# smoothieboard.net
KiCad netlist of a schematic drawn in EAGLE
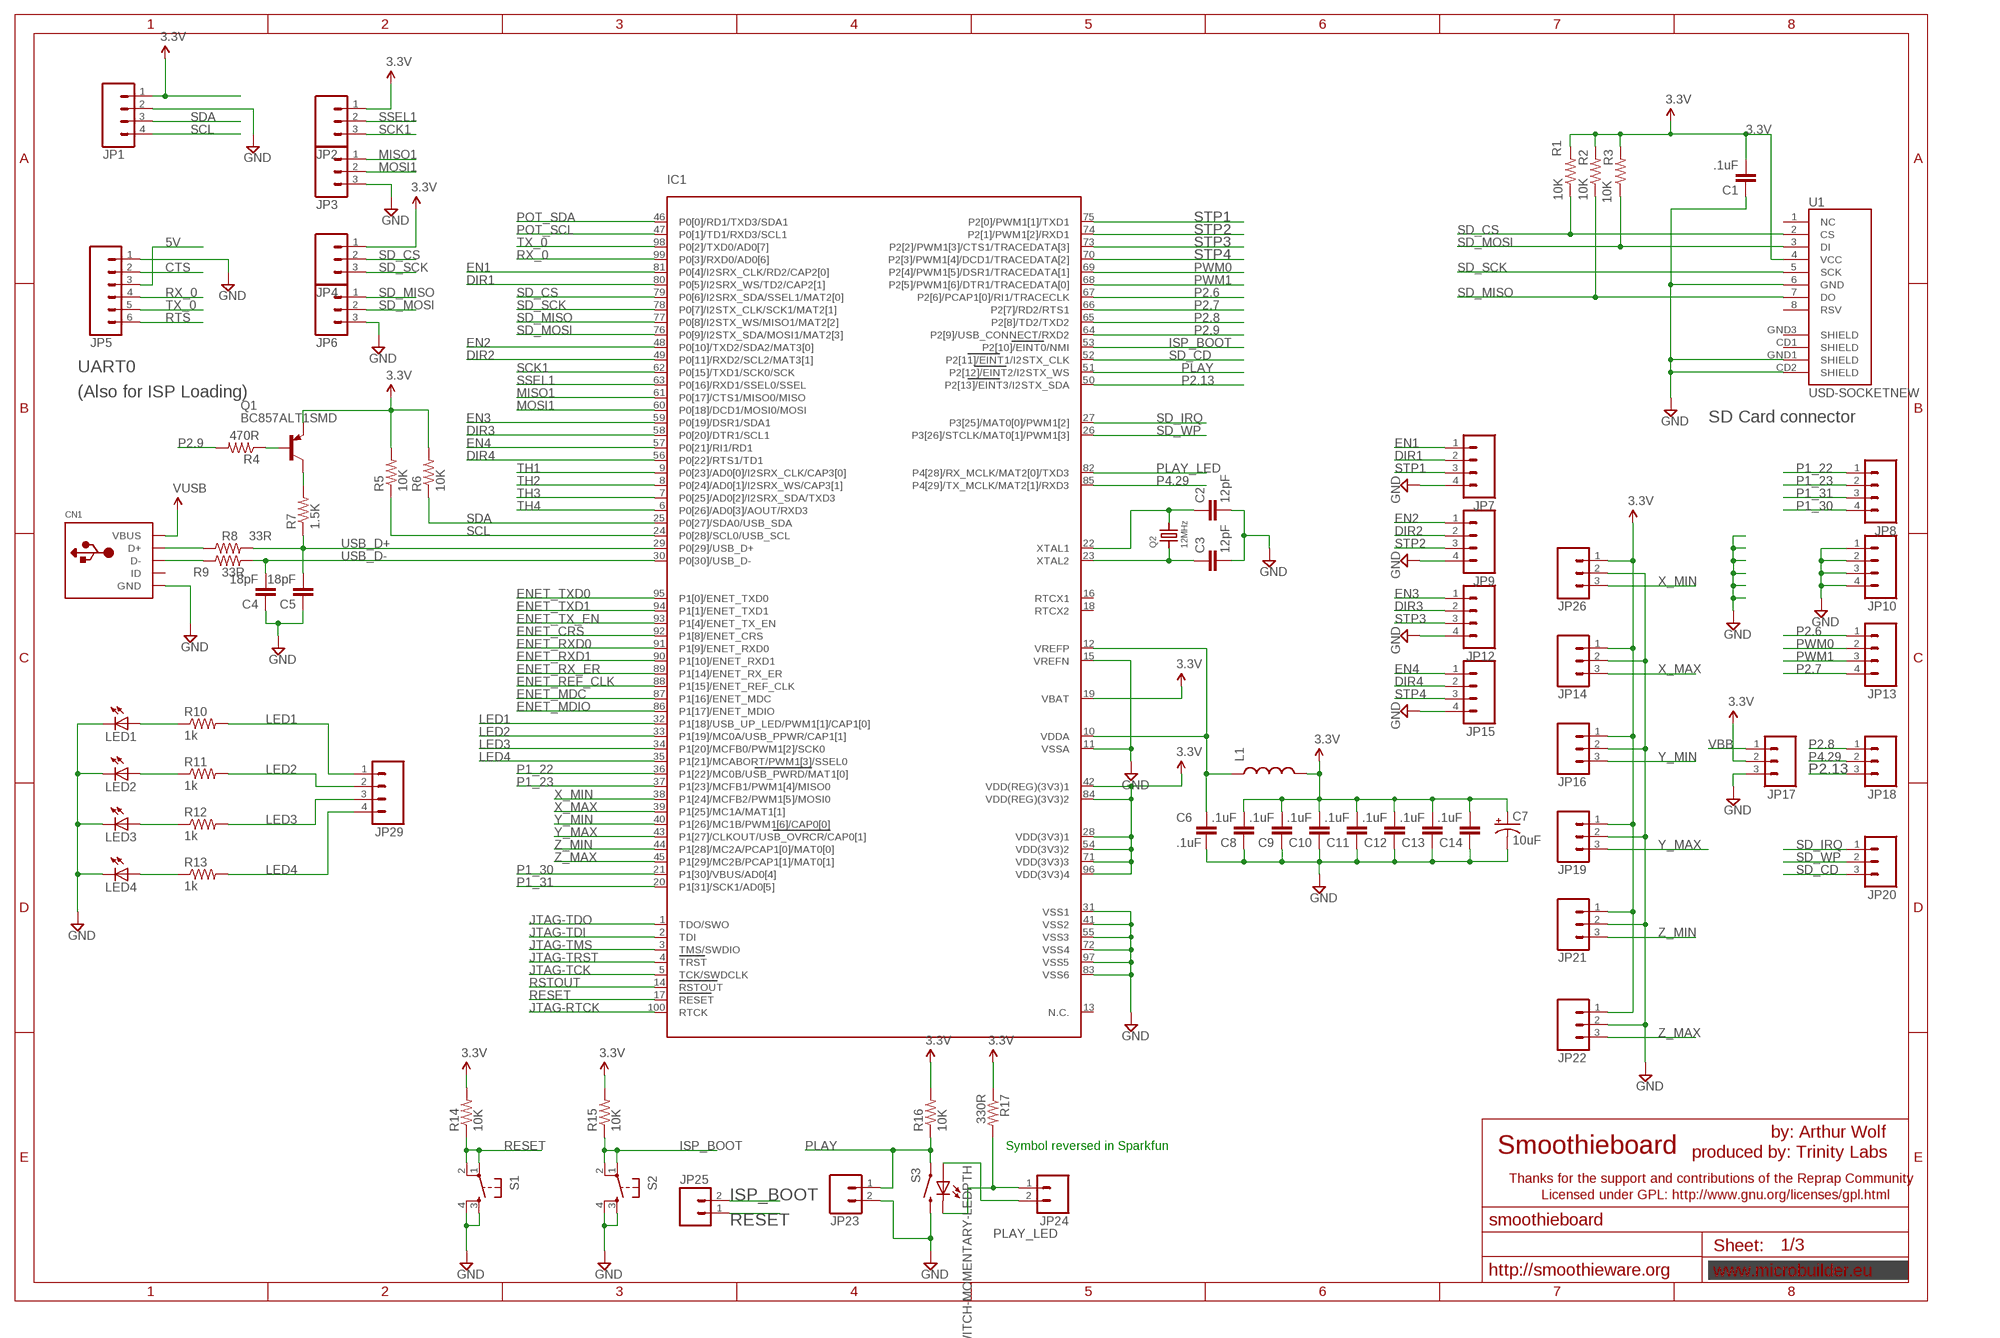
[diagram p0: schematic, sheet 1]
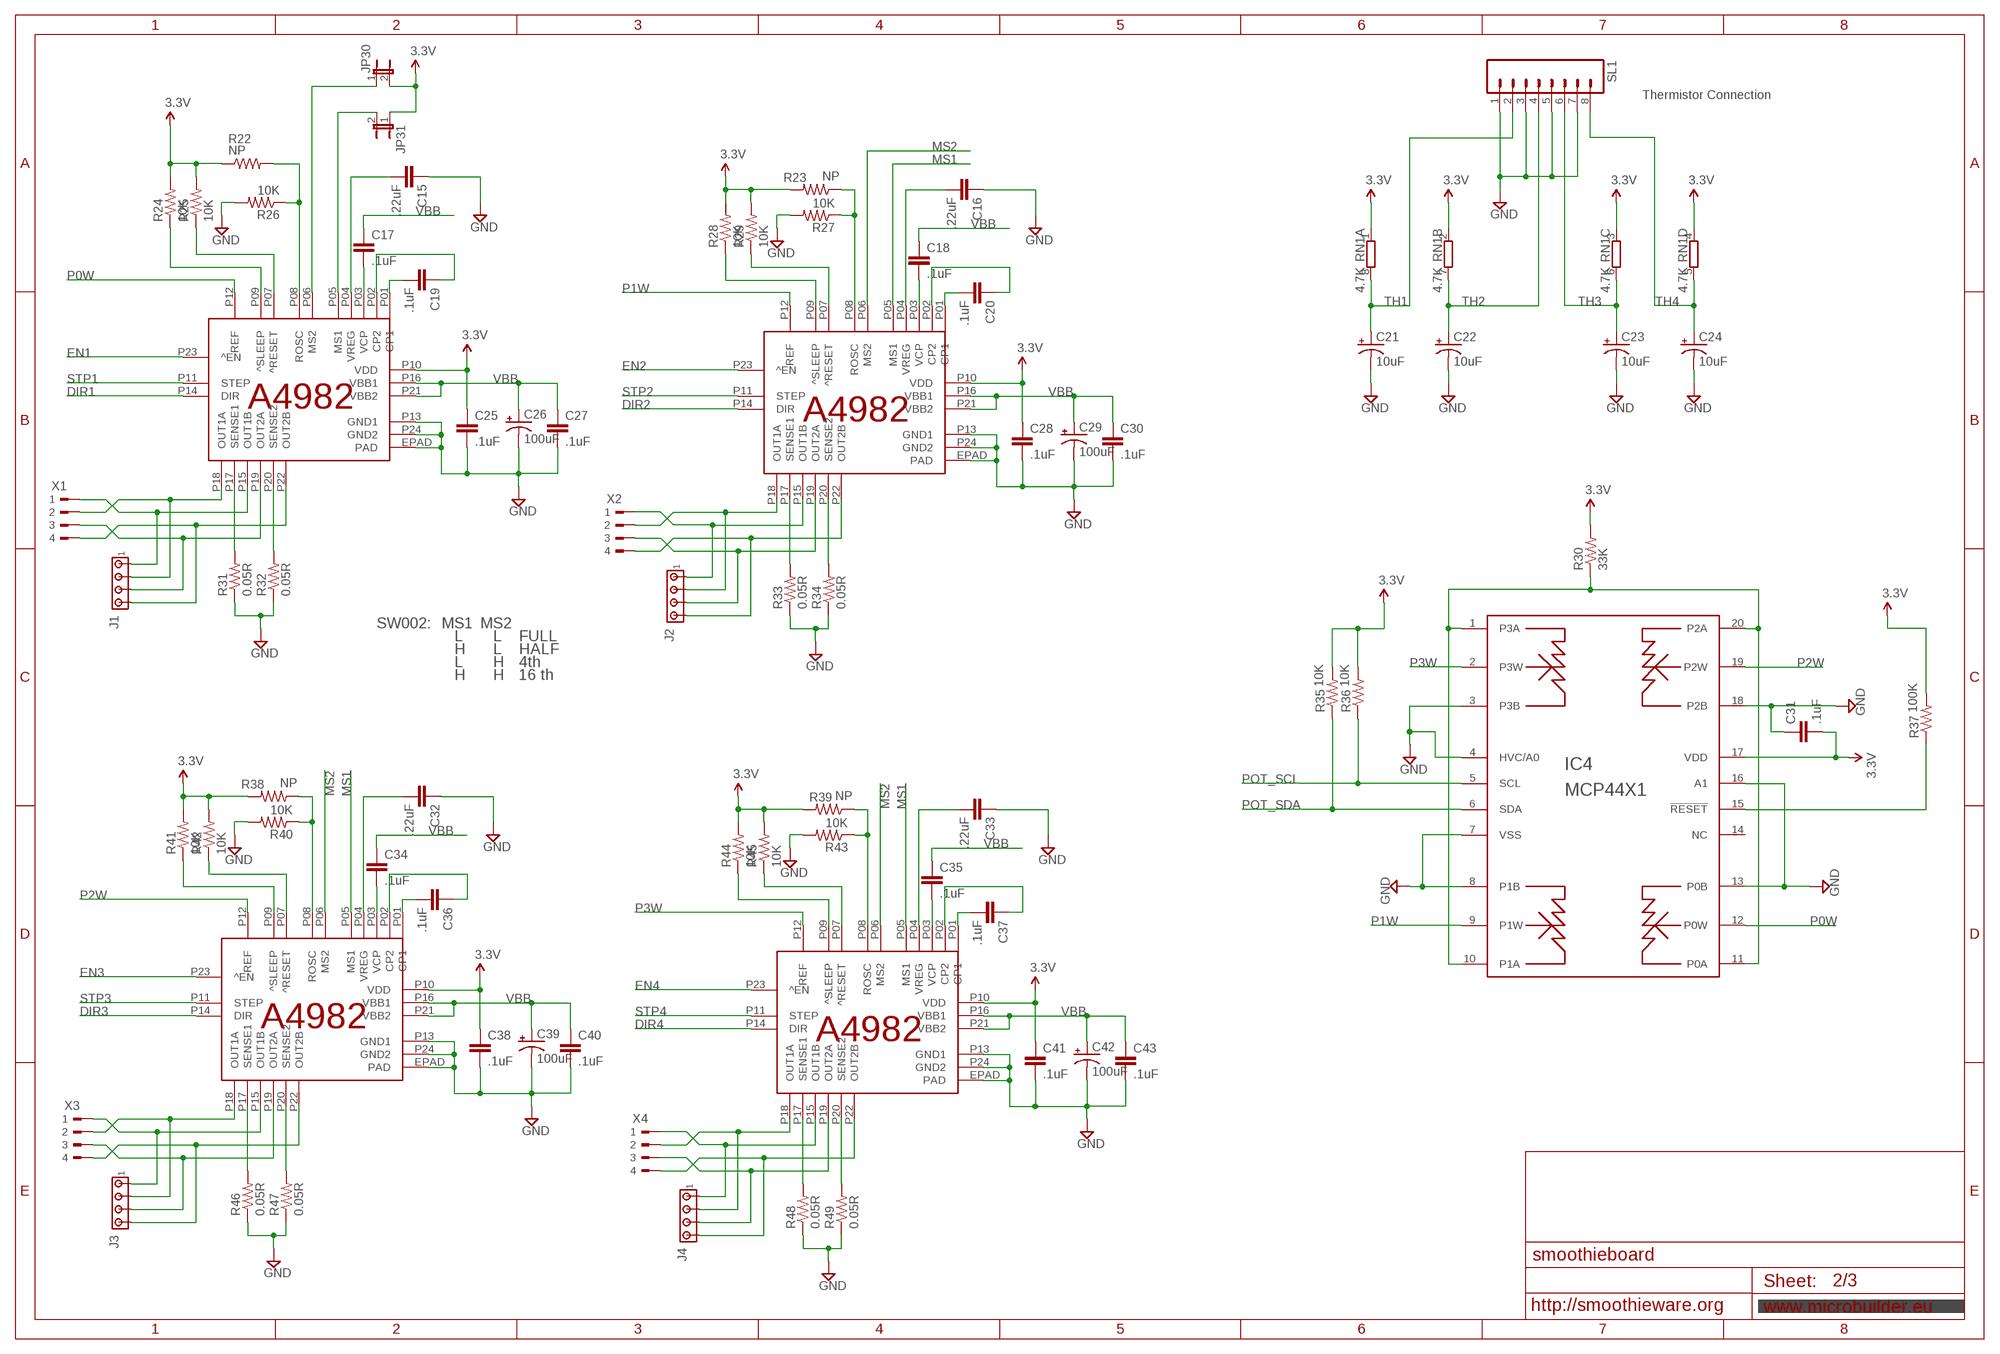
[diagram p1: schematic, sheet 2]
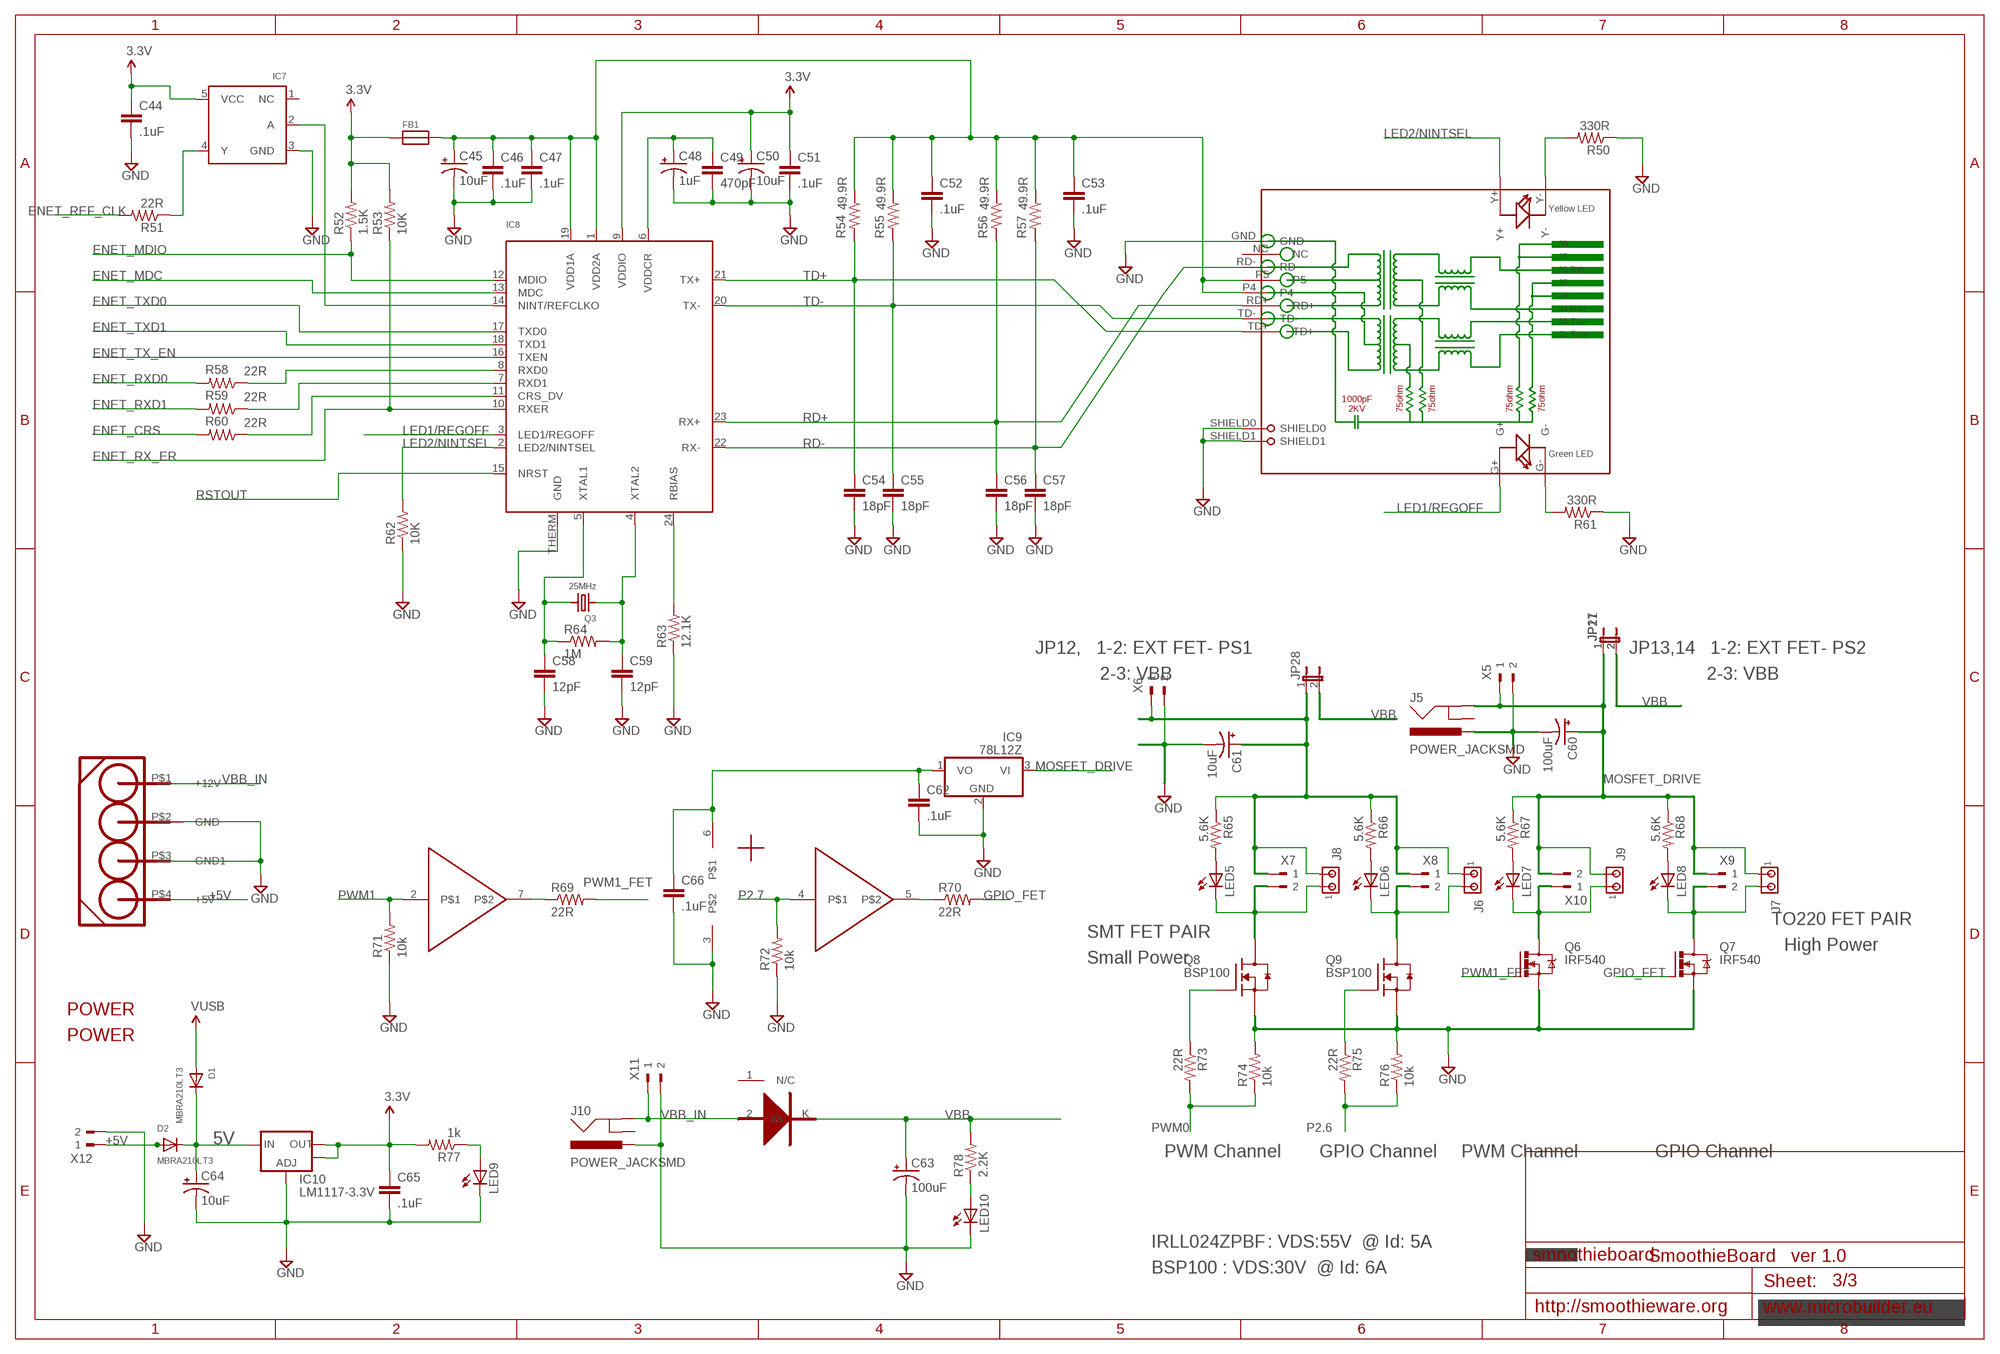
[diagram p2: schematic, sheet 3]

(export (version "E")
  (design (tool "Eeschema 10.0.6"))
  (components
    (comp (ref "C15")
      (value ".22uF")
      (footprint "eagle-import:C0603")
      (libsource (lib "eagle-import") (part "C-EUC0603"))
    )
    (comp (ref "C16")
      (value ".22uF")
      (footprint "eagle-import:C0603")
      (libsource (lib "eagle-import") (part "C-EUC0603"))
    )
    (comp (ref "C17")
      (value ".1uF")
      (footprint "eagle-import:C0603")
      (libsource (lib "eagle-import") (part "C-EUC0603"))
    )
    (comp (ref "C18")
      (value ".1uF")
      (footprint "eagle-import:C0603")
      (libsource (lib "eagle-import") (part "C-EUC0603"))
    )
    (comp (ref "C19")
      (value ".1uF")
      (footprint "eagle-import:C0603")
      (libsource (lib "eagle-import") (part "C-EUC0603"))
    )
    (comp (ref "C20")
      (value ".1uF")
      (footprint "eagle-import:C0603")
      (libsource (lib "eagle-import") (part "C-EUC0603"))
    )
    (comp (ref "C21")
      (value "10uF")
      (footprint "eagle-import:EIA3216")
      (libsource (lib "eagle-import") (part "CAP_POL1206"))
    )
    (comp (ref "C22")
      (value "10uF")
      (footprint "eagle-import:EIA3216")
      (libsource (lib "eagle-import") (part "CAP_POL1206"))
    )
    (comp (ref "C23")
      (value "10uF")
      (footprint "eagle-import:EIA3216")
      (libsource (lib "eagle-import") (part "CAP_POL1206"))
    )
    (comp (ref "C24")
      (value "10uF")
      (footprint "eagle-import:EIA3216")
      (libsource (lib "eagle-import") (part "CAP_POL1206"))
    )
    (comp (ref "C25")
      (value ".1uF")
      (footprint "eagle-import:C0603")
      (libsource (lib "eagle-import") (part "C-EUC0603"))
    )
    (comp (ref "C26")
      (value "100uF")
      (footprint "eagle-import:PANASONIC_E")
      (libsource (lib "eagle-import") (part "CAP_POLE"))
    )
    (comp (ref "C27")
      (value ".1uF")
      (footprint "eagle-import:C0603")
      (libsource (lib "eagle-import") (part "C-EUC0603"))
    )
    (comp (ref "C28")
      (value ".1uF")
      (footprint "eagle-import:C0603")
      (libsource (lib "eagle-import") (part "C-EUC0603"))
    )
    (comp (ref "C29")
      (value "100uF")
      (footprint "eagle-import:PANASONIC_E")
      (libsource (lib "eagle-import") (part "CAP_POLE"))
    )
    (comp (ref "C30")
      (value ".1uF")
      (footprint "eagle-import:C0603")
      (libsource (lib "eagle-import") (part "C-EUC0603"))
    )
    (comp (ref "C31")
      (value ".1uF")
      (footprint "eagle-import:C0603")
      (libsource (lib "eagle-import") (part "C-EUC0603"))
    )
    (comp (ref "C32")
      (value ".22uF")
      (footprint "eagle-import:C0603")
      (libsource (lib "eagle-import") (part "C-EUC0603"))
    )
    (comp (ref "C33")
      (value ".22uF")
      (footprint "eagle-import:C0603")
      (libsource (lib "eagle-import") (part "C-EUC0603"))
    )
    (comp (ref "C34")
      (value ".1uF")
      (footprint "eagle-import:C0603")
      (libsource (lib "eagle-import") (part "C-EUC0603"))
    )
    (comp (ref "C35")
      (value ".1uF")
      (footprint "eagle-import:C0603")
      (libsource (lib "eagle-import") (part "C-EUC0603"))
    )
    (comp (ref "C36")
      (value ".1uF")
      (footprint "eagle-import:C0603")
      (libsource (lib "eagle-import") (part "C-EUC0603"))
    )
    (comp (ref "C37")
      (value ".1uF")
      (footprint "eagle-import:C0603")
      (libsource (lib "eagle-import") (part "C-EUC0603"))
    )
    (comp (ref "C38")
      (value ".1uF")
      (footprint "eagle-import:C0603")
      (libsource (lib "eagle-import") (part "C-EUC0603"))
    )
    (comp (ref "C39")
      (value "100uF")
      (footprint "eagle-import:PANASONIC_E")
      (libsource (lib "eagle-import") (part "CAP_POLE"))
    )
    (comp (ref "C40")
      (value ".1uF")
      (footprint "eagle-import:C0603")
      (libsource (lib "eagle-import") (part "C-EUC0603"))
    )
    (comp (ref "C41")
      (value ".1uF")
      (footprint "eagle-import:C0603")
      (libsource (lib "eagle-import") (part "C-EUC0603"))
    )
    (comp (ref "C42")
      (value "100uF")
      (footprint "eagle-import:PANASONIC_E")
      (libsource (lib "eagle-import") (part "CAP_POLE"))
    )
    (comp (ref "C43")
      (value ".1uF")
      (footprint "eagle-import:C0603")
      (libsource (lib "eagle-import") (part "C-EUC0603"))
    )
    (comp (ref "IC2")
      (value "A4982")
      (footprint "eagle-import:ETSSOP24")
      (libsource (lib "eagle-import") (part "A4982"))
    )
    (comp (ref "IC3")
      (value "A4982")
      (footprint "eagle-import:ETSSOP24")
      (libsource (lib "eagle-import") (part "A4982"))
    )
    (comp (ref "IC4")
      (value "MCP44X1")
      (footprint "eagle-import:TSSOP20")
      (libsource (lib "eagle-import") (part "MCP44X1"))
    )
    (comp (ref "IC5")
      (value "A4982")
      (footprint "eagle-import:ETSSOP24")
      (libsource (lib "eagle-import") (part "A4982"))
    )
    (comp (ref "IC6")
      (value "A4982")
      (footprint "eagle-import:ETSSOP24")
      (libsource (lib "eagle-import") (part "A4982"))
    )
    (comp (ref "J1")
      (value "MTA04-100")
      (footprint "eagle-import:10X04MTA")
      (libsource (lib "eagle-import") (part "MTA04-100"))
    )
    (comp (ref "J2")
      (value "MTA04-100")
      (footprint "eagle-import:10X04MTA")
      (libsource (lib "eagle-import") (part "MTA04-100"))
    )
    (comp (ref "J3")
      (value "MTA04-100")
      (footprint "eagle-import:10X04MTA")
      (libsource (lib "eagle-import") (part "MTA04-100"))
    )
    (comp (ref "J4")
      (value "MTA04-100")
      (footprint "eagle-import:10X04MTA")
      (libsource (lib "eagle-import") (part "MTA04-100"))
    )
    (comp (ref "JP30")
      (value "JUMPER-2SMD-NC")
      (footprint "eagle-import:SJ_2S")
      (libsource (lib "eagle-import") (part "JUMPER-2SMD-NC"))
    )
    (comp (ref "JP31")
      (value "JUMPER-2SMD-NC")
      (footprint "eagle-import:SJ_2S")
      (libsource (lib "eagle-import") (part "JUMPER-2SMD-NC"))
    )
    (comp (ref "R22")
      (value "NP")
      (footprint "eagle-import:R0603")
      (libsource (lib "eagle-import") (part "R-US_R0603"))
    )
    (comp (ref "R23")
      (value "NP")
      (footprint "eagle-import:R0603")
      (libsource (lib "eagle-import") (part "R-US_R0603"))
    )
    (comp (ref "R24")
      (value "10K")
      (footprint "eagle-import:R0603")
      (libsource (lib "eagle-import") (part "R-US_R0603"))
    )
    (comp (ref "R25")
      (value "10K")
      (footprint "eagle-import:R0603")
      (libsource (lib "eagle-import") (part "R-US_R0603"))
    )
    (comp (ref "R26")
      (value "10K")
      (footprint "eagle-import:R0603")
      (libsource (lib "eagle-import") (part "R-US_R0603"))
    )
    (comp (ref "R27")
      (value "10K")
      (footprint "eagle-import:R0603")
      (libsource (lib "eagle-import") (part "R-US_R0603"))
    )
    (comp (ref "R28")
      (value "10K")
      (footprint "eagle-import:R0603")
      (libsource (lib "eagle-import") (part "R-US_R0603"))
    )
    (comp (ref "R29")
      (value "10K")
      (footprint "eagle-import:R0603")
      (libsource (lib "eagle-import") (part "R-US_R0603"))
    )
    (comp (ref "R30")
      (value "33K")
      (footprint "eagle-import:R0603")
      (libsource (lib "eagle-import") (part "R-US_R0603"))
    )
    (comp (ref "R31")
      (value "0.05R")
      (footprint "eagle-import:R2512")
      (libsource (lib "eagle-import") (part "RESISTOR2512"))
    )
    (comp (ref "R32")
      (value "0.05R")
      (footprint "eagle-import:R2512")
      (libsource (lib "eagle-import") (part "RESISTOR2512"))
    )
    (comp (ref "R33")
      (value "0.05R")
      (footprint "eagle-import:R2512")
      (libsource (lib "eagle-import") (part "RESISTOR2512"))
    )
    (comp (ref "R34")
      (value "0.05R")
      (footprint "eagle-import:R2512")
      (libsource (lib "eagle-import") (part "RESISTOR2512"))
    )
    (comp (ref "R35")
      (value "10K")
      (footprint "eagle-import:R0603")
      (libsource (lib "eagle-import") (part "R-US_R0603"))
    )
    (comp (ref "R36")
      (value "10K")
      (footprint "eagle-import:R0603")
      (libsource (lib "eagle-import") (part "R-US_R0603"))
    )
    (comp (ref "R37")
      (value "100K")
      (footprint "eagle-import:R0603")
      (libsource (lib "eagle-import") (part "R-US_R0603"))
    )
    (comp (ref "R38")
      (value "NP")
      (footprint "eagle-import:R0603")
      (libsource (lib "eagle-import") (part "R-US_R0603"))
    )
    (comp (ref "R39")
      (value "NP")
      (footprint "eagle-import:R0603")
      (libsource (lib "eagle-import") (part "R-US_R0603"))
    )
    (comp (ref "R40")
      (value "10K")
      (footprint "eagle-import:R0603")
      (libsource (lib "eagle-import") (part "R-US_R0603"))
    )
    (comp (ref "R41")
      (value "10K")
      (footprint "eagle-import:R0603")
      (libsource (lib "eagle-import") (part "R-US_R0603"))
    )
    (comp (ref "R42")
      (value "10K")
      (footprint "eagle-import:R0603")
      (libsource (lib "eagle-import") (part "R-US_R0603"))
    )
    (comp (ref "R43")
      (value "10K")
      (footprint "eagle-import:R0603")
      (libsource (lib "eagle-import") (part "R-US_R0603"))
    )
    (comp (ref "R44")
      (value "10K")
      (footprint "eagle-import:R0603")
      (libsource (lib "eagle-import") (part "R-US_R0603"))
    )
    (comp (ref "R45")
      (value "10K")
      (footprint "eagle-import:R0603")
      (libsource (lib "eagle-import") (part "R-US_R0603"))
    )
    (comp (ref "R46")
      (value "0.05R")
      (footprint "eagle-import:R2512")
      (libsource (lib "eagle-import") (part "RESISTOR2512"))
    )
    (comp (ref "R47")
      (value "0.05R")
      (footprint "eagle-import:R2512")
      (libsource (lib "eagle-import") (part "RESISTOR2512"))
    )
    (comp (ref "R48")
      (value "0.05R")
      (footprint "eagle-import:R2512")
      (libsource (lib "eagle-import") (part "RESISTOR2512"))
    )
    (comp (ref "R49")
      (value "0.05R")
      (footprint "eagle-import:R2512")
      (libsource (lib "eagle-import") (part "RESISTOR2512"))
    )
    (comp (ref "RN1")
      (value "4.7K")
      (footprint "eagle-import:0603-ARV")
      (libsource (lib "eagle-import") (part "4R-N0603-ARV"))
    )
    (comp (ref "SL1")
      (value "M08")
      (footprint "eagle-import:08P")
      (libsource (lib "eagle-import") (part "M08"))
    )
    (comp (ref "X1")
      (value "180G-4")
      (footprint "eagle-import:180G-4")
      (libsource (lib "eagle-import") (part "180G-4"))
    )
    (comp (ref "X2")
      (value "180G-4")
      (footprint "eagle-import:180G-4")
      (libsource (lib "eagle-import") (part "180G-4"))
    )
    (comp (ref "X3")
      (value "180G-4")
      (footprint "eagle-import:180G-4")
      (libsource (lib "eagle-import") (part "180G-4"))
    )
    (comp (ref "X4")
      (value "180G-4")
      (footprint "eagle-import:180G-4")
      (libsource (lib "eagle-import") (part "180G-4"))
    )
    (comp (ref "C1")
      (value ".1uF")
      (footprint "eagle-import:C0603")
      (libsource (lib "eagle-import") (part "resistor_C-EUC0603"))
    )
    (comp (ref "C2")
      (value "12pF")
      (footprint "eagle-import:C0603")
      (libsource (lib "eagle-import") (part "C-EUC0603"))
    )
    (comp (ref "C3")
      (value "12pF")
      (footprint "eagle-import:C0603")
      (libsource (lib "eagle-import") (part "C-EUC0603"))
    )
    (comp (ref "C4")
      (value "18pF")
      (footprint "eagle-import:C0603")
      (libsource (lib "eagle-import") (part "C-EUC0603"))
    )
    (comp (ref "C5")
      (value "18pF")
      (footprint "eagle-import:C0603")
      (libsource (lib "eagle-import") (part "C-EUC0603"))
    )
    (comp (ref "C6")
      (value ".1uF")
      (footprint "eagle-import:C0603")
      (libsource (lib "eagle-import") (part "C-EUC0603"))
    )
    (comp (ref "C7")
      (value "10uF")
      (footprint "eagle-import:EIA3216")
      (libsource (lib "eagle-import") (part "CAP_POL1206"))
    )
    (comp (ref "C8")
      (value ".1uF")
      (footprint "eagle-import:C0603")
      (libsource (lib "eagle-import") (part "C-EUC0603"))
    )
    (comp (ref "C9")
      (value ".1uF")
      (footprint "eagle-import:C0603")
      (libsource (lib "eagle-import") (part "C-EUC0603"))
    )
    (comp (ref "C10")
      (value ".1uF")
      (footprint "eagle-import:C0603")
      (libsource (lib "eagle-import") (part "C-EUC0603"))
    )
    (comp (ref "C11")
      (value ".1uF")
      (footprint "eagle-import:C0603")
      (libsource (lib "eagle-import") (part "C-EUC0603"))
    )
    (comp (ref "C12")
      (value ".1uF")
      (footprint "eagle-import:C0603")
      (libsource (lib "eagle-import") (part "C-EUC0603"))
    )
    (comp (ref "C13")
      (value ".1uF")
      (footprint "eagle-import:C0603")
      (libsource (lib "eagle-import") (part "C-EUC0603"))
    )
    (comp (ref "C14")
      (value ".1uF")
      (footprint "eagle-import:C0603")
      (libsource (lib "eagle-import") (part "C-EUC0603"))
    )
    (comp (ref "CN1")
      (value "USBMINIB")
      (footprint "eagle-import:USB-MINIB")
      (libsource (lib "eagle-import") (part "USBMINIB"))
    )
    (comp (ref "IC1")
      (value "LPC1768")
      (footprint "eagle-import:LQFP100")
      (libsource (lib "eagle-import") (part "LPC1768"))
    )
    (comp (ref "JP1")
      (value "M041X04_NO_SILK")
      (footprint "eagle-import:1X04_NO_SILK")
      (libsource (lib "eagle-import") (part "M041X04_NO_SILK"))
    )
    (comp (ref "JP2")
      (value "M031X03_NO_SILK")
      (footprint "eagle-import:1X03_NO_SILK")
      (libsource (lib "eagle-import") (part "M031X03_NO_SILK"))
    )
    (comp (ref "JP3")
      (value "M031X03_NO_SILK")
      (footprint "eagle-import:1X03_NO_SILK")
      (libsource (lib "eagle-import") (part "M031X03_NO_SILK"))
    )
    (comp (ref "JP4")
      (value "M031X03_NO_SILK")
      (footprint "eagle-import:1X03_NO_SILK")
      (libsource (lib "eagle-import") (part "M031X03_NO_SILK"))
    )
    (comp (ref "JP5")
      (value "M06POLAR")
      (footprint "eagle-import:MOLEX-1X6")
      (libsource (lib "eagle-import") (part "M06POLAR"))
    )
    (comp (ref "JP6")
      (value "M031X03_NO_SILK")
      (footprint "eagle-import:1X03_NO_SILK")
      (libsource (lib "eagle-import") (part "M031X03_NO_SILK"))
    )
    (comp (ref "JP7")
      (value "M041X04_NO_SILK")
      (footprint "eagle-import:1X04_NO_SILK")
      (libsource (lib "eagle-import") (part "M041X04_NO_SILK"))
    )
    (comp (ref "JP8")
      (value "M041X04_NO_SILK")
      (footprint "eagle-import:1X04_NO_SILK")
      (libsource (lib "eagle-import") (part "M041X04_NO_SILK"))
    )
    (comp (ref "JP9")
      (value "M041X04_NO_SILK")
      (footprint "eagle-import:1X04_NO_SILK")
      (libsource (lib "eagle-import") (part "M041X04_NO_SILK"))
    )
    (comp (ref "JP10")
      (value "M041X04_NO_SILK")
      (footprint "eagle-import:1X04_NO_SILK")
      (libsource (lib "eagle-import") (part "M041X04_NO_SILK"))
    )
    (comp (ref "JP12")
      (value "M041X04_NO_SILK")
      (footprint "eagle-import:1X04_NO_SILK")
      (libsource (lib "eagle-import") (part "M041X04_NO_SILK"))
    )
    (comp (ref "JP13")
      (value "M041X04_NO_SILK")
      (footprint "eagle-import:1X04_NO_SILK")
      (libsource (lib "eagle-import") (part "M041X04_NO_SILK"))
    )
    (comp (ref "JP14")
      (value "M03POLAR")
      (footprint "eagle-import:MOLEX-1X3")
      (libsource (lib "eagle-import") (part "M03POLAR"))
    )
    (comp (ref "JP15")
      (value "M041X04_NO_SILK")
      (footprint "eagle-import:1X04_NO_SILK")
      (libsource (lib "eagle-import") (part "M041X04_NO_SILK"))
    )
    (comp (ref "JP16")
      (value "M03POLAR")
      (footprint "eagle-import:MOLEX-1X3")
      (libsource (lib "eagle-import") (part "M03POLAR"))
    )
    (comp (ref "JP17")
      (value "M03PTH")
      (footprint "eagle-import:1X03")
      (libsource (lib "eagle-import") (part "M03PTH"))
    )
    (comp (ref "JP18")
      (value "M03PTH")
      (footprint "eagle-import:1X03")
      (libsource (lib "eagle-import") (part "M03PTH"))
    )
    (comp (ref "JP19")
      (value "M03POLAR")
      (footprint "eagle-import:MOLEX-1X3")
      (libsource (lib "eagle-import") (part "M03POLAR"))
    )
    (comp (ref "JP20")
      (value "M03PTH")
      (footprint "eagle-import:1X03")
      (libsource (lib "eagle-import") (part "M03PTH"))
    )
    (comp (ref "JP21")
      (value "M03POLAR")
      (footprint "eagle-import:MOLEX-1X3")
      (libsource (lib "eagle-import") (part "M03POLAR"))
    )
    (comp (ref "JP22")
      (value "M03POLAR")
      (footprint "eagle-import:MOLEX-1X3")
      (libsource (lib "eagle-import") (part "M03POLAR"))
    )
    (comp (ref "JP23")
      (value "M02PTH")
      (footprint "eagle-import:1X02")
      (libsource (lib "eagle-import") (part "M02PTH"))
    )
    (comp (ref "JP24")
      (value "M02PTH")
      (footprint "eagle-import:1X02")
      (libsource (lib "eagle-import") (part "M02PTH"))
    )
    (comp (ref "JP25")
      (value "M02PTH")
      (footprint "eagle-import:1X02")
      (libsource (lib "eagle-import") (part "M02PTH"))
    )
    (comp (ref "JP26")
      (value "M03POLAR")
      (footprint "eagle-import:MOLEX-1X3")
      (libsource (lib "eagle-import") (part "M03POLAR"))
    )
    (comp (ref "JP29")
      (value "M041X04_NO_SILK")
      (footprint "eagle-import:1X04_NO_SILK")
      (libsource (lib "eagle-import") (part "M041X04_NO_SILK"))
    )
    (comp (ref "L1")
      (value "INDUCTOR0603")
      (footprint "eagle-import:0603")
      (libsource (lib "eagle-import") (part "INDUCTOR0603"))
    )
    (comp (ref "LED1")
      (value "LEDCHIP-LED0805")
      (footprint "eagle-import:CHIP-LED0805")
      (libsource (lib "eagle-import") (part "LEDCHIP-LED0805"))
    )
    (comp (ref "LED2")
      (value "LEDCHIP-LED0805")
      (footprint "eagle-import:CHIP-LED0805")
      (libsource (lib "eagle-import") (part "LEDCHIP-LED0805"))
    )
    (comp (ref "LED3")
      (value "LEDCHIP-LED0805")
      (footprint "eagle-import:CHIP-LED0805")
      (libsource (lib "eagle-import") (part "LEDCHIP-LED0805"))
    )
    (comp (ref "LED4")
      (value "LEDCHIP-LED0805")
      (footprint "eagle-import:CHIP-LED0805")
      (libsource (lib "eagle-import") (part "LEDCHIP-LED0805"))
    )
    (comp (ref "Q1")
      (value "BC857ALT1SMD")
      (footprint "eagle-import:SOT23-BEC")
      (libsource (lib "eagle-import") (part "BC857SMDALT1"))
    )
    (comp (ref "Q2")
      (value "12MHz")
      (footprint "eagle-import:CRYSTAL_3.2X2.5")
      (libsource (lib "eagle-import") (part "CRYSTALTHIN"))
    )
    (comp (ref "R1")
      (value "10K")
      (footprint "eagle-import:R0603")
      (libsource (lib "eagle-import") (part "R-US_R0603"))
    )
    (comp (ref "R2")
      (value "10K")
      (footprint "eagle-import:R0603")
      (libsource (lib "eagle-import") (part "R-US_R0603"))
    )
    (comp (ref "R3")
      (value "10K")
      (footprint "eagle-import:R0603")
      (libsource (lib "eagle-import") (part "R-US_R0603"))
    )
    (comp (ref "R4")
      (value "470R")
      (footprint "eagle-import:R0603")
      (libsource (lib "eagle-import") (part "R-US_R0603"))
    )
    (comp (ref "R5")
      (value "10K")
      (footprint "eagle-import:R0603")
      (libsource (lib "eagle-import") (part "R-US_R0603"))
    )
    (comp (ref "R6")
      (value "10K")
      (footprint "eagle-import:R0603")
      (libsource (lib "eagle-import") (part "R-US_R0603"))
    )
    (comp (ref "R7")
      (value "1.5K")
      (footprint "eagle-import:R0603")
      (libsource (lib "eagle-import") (part "R-US_R0603"))
    )
    (comp (ref "R8")
      (value "33R")
      (footprint "eagle-import:R0603")
      (libsource (lib "eagle-import") (part "R-US_R0603"))
    )
    (comp (ref "R9")
      (value "33R")
      (footprint "eagle-import:R0603")
      (libsource (lib "eagle-import") (part "R-US_R0603"))
    )
    (comp (ref "R10")
      (value "1k")
      (footprint "eagle-import:R0603")
      (libsource (lib "eagle-import") (part "R-US_R0603"))
    )
    (comp (ref "R11")
      (value "1k")
      (footprint "eagle-import:R0603")
      (libsource (lib "eagle-import") (part "R-US_R0603"))
    )
    (comp (ref "R12")
      (value "1k")
      (footprint "eagle-import:R0603")
      (libsource (lib "eagle-import") (part "R-US_R0603"))
    )
    (comp (ref "R13")
      (value "1k")
      (footprint "eagle-import:R0603")
      (libsource (lib "eagle-import") (part "R-US_R0603"))
    )
    (comp (ref "R14")
      (value "10K")
      (footprint "eagle-import:R0603")
      (libsource (lib "eagle-import") (part "R-US_R0603"))
    )
    (comp (ref "R15")
      (value "10K")
      (footprint "eagle-import:R0603")
      (libsource (lib "eagle-import") (part "R-US_R0603"))
    )
    (comp (ref "R16")
      (value "10K")
      (footprint "eagle-import:R0603")
      (libsource (lib "eagle-import") (part "R-US_R0603"))
    )
    (comp (ref "R17")
      (value "330R")
      (footprint "eagle-import:R0603")
      (libsource (lib "eagle-import") (part "R-US_R0603"))
    )
    (comp (ref "S1")
      (value "TAC_SWITCHSMD")
      (footprint "eagle-import:TACTILE_SWITCH_SMD")
      (libsource (lib "eagle-import") (part "TAC_SWITCHSMD"))
    )
    (comp (ref "S2")
      (value "TAC_SWITCHSMD")
      (footprint "eagle-import:TACTILE_SWITCH_SMD")
      (libsource (lib "eagle-import") (part "TAC_SWITCHSMD"))
    )
    (comp (ref "S3")
      (value "SWITCH-MOMENTARY-LEDPTH")
      (footprint "eagle-import:TACTILE-PTH-LED-12MM")
      (libsource (lib "eagle-import") (part "SWITCH-MOMENTARY-LEDPTH"))
    )
    (comp (ref "U1")
      (value "USD-SOCKETNEW")
      (footprint "eagle-import:MICRO-SD-SOCKET-PP")
      (libsource (lib "eagle-import") (part "USD-SOCKETNEW"))
    )
    (comp (ref "C44")
      (value ".1uF")
      (footprint "eagle-import:C0603")
      (libsource (lib "eagle-import") (part "resistor_C-EUC0603"))
    )
    (comp (ref "C45")
      (value "10uF")
      (footprint "eagle-import:EIA3216")
      (libsource (lib "eagle-import") (part "CAP_POL1206"))
    )
    (comp (ref "C46")
      (value ".1uF")
      (footprint "eagle-import:C0603")
      (libsource (lib "eagle-import") (part "resistor_C-EUC0603"))
    )
    (comp (ref "C47")
      (value ".1uF")
      (footprint "eagle-import:C0603")
      (libsource (lib "eagle-import") (part "resistor_C-EUC0603"))
    )
    (comp (ref "C48")
      (value "1uF")
      (footprint "eagle-import:EIA3216")
      (libsource (lib "eagle-import") (part "CAP_POL1206"))
    )
    (comp (ref "C49")
      (value "470pF")
      (footprint "eagle-import:C0603K")
      (libsource (lib "eagle-import") (part "resistor_C-EUC0603K"))
    )
    (comp (ref "C50")
      (value "10uF")
      (footprint "eagle-import:EIA3216")
      (libsource (lib "eagle-import") (part "CAP_POL1206"))
    )
    (comp (ref "C51")
      (value ".1uF")
      (footprint "eagle-import:C0603")
      (libsource (lib "eagle-import") (part "resistor_C-EUC0603"))
    )
    (comp (ref "C52")
      (value ".1uF")
      (footprint "eagle-import:C0603")
      (libsource (lib "eagle-import") (part "resistor_C-EUC0603"))
    )
    (comp (ref "C53")
      (value ".1uF")
      (footprint "eagle-import:C0603")
      (libsource (lib "eagle-import") (part "resistor_C-EUC0603"))
    )
    (comp (ref "C54")
      (value "18pF")
      (footprint "eagle-import:C0603")
      (libsource (lib "eagle-import") (part "resistor_C-EUC0603"))
    )
    (comp (ref "C55")
      (value "18pF")
      (footprint "eagle-import:C0603")
      (libsource (lib "eagle-import") (part "resistor_C-EUC0603"))
    )
    (comp (ref "C56")
      (value "18pF")
      (footprint "eagle-import:C0603")
      (libsource (lib "eagle-import") (part "resistor_C-EUC0603"))
    )
    (comp (ref "C57")
      (value "18pF")
      (footprint "eagle-import:C0603")
      (libsource (lib "eagle-import") (part "resistor_C-EUC0603"))
    )
    (comp (ref "C58")
      (value "12pF")
      (footprint "eagle-import:C0603")
      (libsource (lib "eagle-import") (part "resistor_C-EUC0603"))
    )
    (comp (ref "C59")
      (value "12pF")
      (footprint "eagle-import:C0603")
      (libsource (lib "eagle-import") (part "resistor_C-EUC0603"))
    )
    (comp (ref "C60")
      (value "100uF")
      (footprint "eagle-import:PANASONIC_E")
      (libsource (lib "eagle-import") (part "CAP_POLE"))
    )
    (comp (ref "C61")
      (value "10uF")
      (footprint "eagle-import:EIA3216")
      (libsource (lib "eagle-import") (part "CAP_POL1206"))
    )
    (comp (ref "C62")
      (value ".1uF")
      (footprint "eagle-import:C0603")
      (libsource (lib "eagle-import") (part "resistor_C-EUC0603"))
    )
    (comp (ref "C63")
      (value "100uF")
      (footprint "eagle-import:PANASONIC_D")
      (libsource (lib "eagle-import") (part "CAP_POLD"))
    )
    (comp (ref "C64")
      (value "10uF")
      (footprint "eagle-import:EIA3216")
      (libsource (lib "eagle-import") (part "CAP_POL1206"))
    )
    (comp (ref "C65")
      (value ".1uF")
      (footprint "eagle-import:C0603")
      (libsource (lib "eagle-import") (part "resistor_C-EUC0603"))
    )
    (comp (ref "C66")
      (value ".1uF")
      (footprint "eagle-import:C0603")
      (libsource (lib "eagle-import") (part "resistor_C-EUC0603"))
    )
    (comp (ref "D1")
      (value "MBRA210LT3")
      (footprint "eagle-import:SMADIODE")
      (libsource (lib "eagle-import") (part "DIODESMA"))
    )
    (comp (ref "D2")
      (value "MBRA210LT3")
      (footprint "eagle-import:SMADIODE")
      (libsource (lib "eagle-import") (part "DIODESMA"))
    )
    (comp (ref "FB1")
      (value "FERRITE")
      (footprint "eagle-import:0603")
      (libsource (lib "eagle-import") (part "FERRITE"))
    )
    (comp (ref "IC7")
      (value "74LVC1G04")
      (footprint "eagle-import:SOT23-5")
      (libsource (lib "eagle-import") (part "74LVC1G04"))
    )
    (comp (ref "IC8")
      (value "LAN8720")
      (footprint "eagle-import:QFN24_4MM")
      (libsource (lib "eagle-import") (part "LAN8720"))
    )
    (comp (ref "IC9")
      (value "78L12Z")
      (footprint "eagle-import:TO92")
      (libsource (lib "eagle-import") (part "78ZL05"))
    )
    (comp (ref "IC10")
      (value "LM1117-3.3V")
      (footprint "eagle-import:SOT223")
      (libsource (lib "eagle-import") (part "V_REG_LM1117SOT223"))
    )
    (comp (ref "J5")
      (value "POWER_JACKSMD")
      (footprint "eagle-import:POWER_JACK_SMD")
      (libsource (lib "eagle-import") (part "POWER_JACKSMD"))
    )
    (comp (ref "J6")
      (value "MTA02-100")
      (footprint "eagle-import:10X02MTA")
      (libsource (lib "eagle-import") (part "MTA02-100"))
    )
    (comp (ref "J7")
      (value "MTA02-100")
      (footprint "eagle-import:10X02MTA")
      (libsource (lib "eagle-import") (part "MTA02-100"))
    )
    (comp (ref "J8")
      (value "MTA02-100")
      (footprint "eagle-import:10X02MTA")
      (libsource (lib "eagle-import") (part "MTA02-100"))
    )
    (comp (ref "J9")
      (value "MTA02-100")
      (footprint "eagle-import:10X02MTA")
      (libsource (lib "eagle-import") (part "MTA02-100"))
    )
    (comp (ref "J10")
      (value "POWER_JACKSMD")
      (footprint "eagle-import:POWER_JACK_SMD")
      (libsource (lib "eagle-import") (part "POWER_JACKSMD"))
    )
    (comp (ref "JP11")
      (value "JP1E")
      (footprint "eagle-import:JP1")
      (libsource (lib "eagle-import") (part "JP1E"))
    )
    (comp (ref "JP27")
      (value "JP1E")
      (footprint "eagle-import:JP1")
      (libsource (lib "eagle-import") (part "JP1E"))
    )
    (comp (ref "JP28")
      (value "JP1E")
      (footprint "eagle-import:JP1")
      (libsource (lib "eagle-import") (part "JP1E"))
    )
    (comp (ref "LED5")
      (value "LEDCHIP-LED0805")
      (footprint "eagle-import:CHIP-LED0805")
      (libsource (lib "eagle-import") (part "LEDCHIP-LED0805"))
    )
    (comp (ref "LED6")
      (value "LEDCHIP-LED0805")
      (footprint "eagle-import:CHIP-LED0805")
      (libsource (lib "eagle-import") (part "LEDCHIP-LED0805"))
    )
    (comp (ref "LED7")
      (value "LEDCHIP-LED0805")
      (footprint "eagle-import:CHIP-LED0805")
      (libsource (lib "eagle-import") (part "LEDCHIP-LED0805"))
    )
    (comp (ref "LED8")
      (value "LEDCHIP-LED0805")
      (footprint "eagle-import:CHIP-LED0805")
      (libsource (lib "eagle-import") (part "LEDCHIP-LED0805"))
    )
    (comp (ref "LED9")
      (value "LEDCHIP-LED0805")
      (footprint "eagle-import:CHIP-LED0805")
      (libsource (lib "eagle-import") (part "LEDCHIP-LED0805"))
    )
    (comp (ref "LED10")
      (value "LEDCHIP-LED0805")
      (footprint "eagle-import:CHIP-LED0805")
      (libsource (lib "eagle-import") (part "LEDCHIP-LED0805"))
    )
    (comp (ref "POWER")
      (value "POWER")
      (footprint "eagle-import:MOLEX8981")
      (libsource (lib "eagle-import") (part "HDD-ATX_CON"))
    )
    (comp (ref "Q3")
      (value "25MHz")
      (footprint "eagle-import:CRYSTAL_3.2X2.5")
      (libsource (lib "eagle-import") (part "CRYSTALTHIN"))
    )
    (comp (ref "Q6")
      (value "IRF540")
      (footprint "eagle-import:TO220BV")
      (libsource (lib "eagle-import") (part "IRF540"))
    )
    (comp (ref "Q7")
      (value "IRF540")
      (footprint "eagle-import:TO220BV")
      (libsource (lib "eagle-import") (part "IRF540"))
    )
    (comp (ref "Q8")
      (value "BSP100")
      (footprint "eagle-import:SOT230P700X160-4N")
      (libsource (lib "eagle-import") (part "MOSFET-NCH_SOT-223"))
    )
    (comp (ref "Q9")
      (value "BSP100")
      (footprint "eagle-import:SOT230P700X160-4N")
      (libsource (lib "eagle-import") (part "MOSFET-NCH_SOT-223"))
    )
    (comp (ref "R50")
      (value "330R")
      (footprint "eagle-import:R0603")
      (libsource (lib "eagle-import") (part "R-US_R0603"))
    )
    (comp (ref "R51")
      (value "22R")
      (footprint "eagle-import:R0603")
      (libsource (lib "eagle-import") (part "R-US_R0603"))
    )
    (comp (ref "R52")
      (value "1.5K")
      (footprint "eagle-import:R0603")
      (libsource (lib "eagle-import") (part "R-US_R0603"))
    )
    (comp (ref "R53")
      (value "10K")
      (footprint "eagle-import:R0603")
      (libsource (lib "eagle-import") (part "R-US_R0603"))
    )
    (comp (ref "R54")
      (value "49.9R")
      (footprint "eagle-import:R0603")
      (libsource (lib "eagle-import") (part "R-US_R0603"))
    )
    (comp (ref "R55")
      (value "49.9R")
      (footprint "eagle-import:R0603")
      (libsource (lib "eagle-import") (part "R-US_R0603"))
    )
    (comp (ref "R56")
      (value "49.9R")
      (footprint "eagle-import:R0603")
      (libsource (lib "eagle-import") (part "R-US_R0603"))
    )
    (comp (ref "R57")
      (value "49.9R")
      (footprint "eagle-import:R0603")
      (libsource (lib "eagle-import") (part "R-US_R0603"))
    )
    (comp (ref "R58")
      (value "22R")
      (footprint "eagle-import:R0603")
      (libsource (lib "eagle-import") (part "R-US_R0603"))
    )
    (comp (ref "R59")
      (value "22R")
      (footprint "eagle-import:R0603")
      (libsource (lib "eagle-import") (part "R-US_R0603"))
    )
    (comp (ref "R60")
      (value "22R")
      (footprint "eagle-import:R0603")
      (libsource (lib "eagle-import") (part "R-US_R0603"))
    )
    (comp (ref "R61")
      (value "330R")
      (footprint "eagle-import:R0603")
      (libsource (lib "eagle-import") (part "R-US_R0603"))
    )
    (comp (ref "R62")
      (value "10K")
      (footprint "eagle-import:R0603")
      (libsource (lib "eagle-import") (part "R-US_R0603"))
    )
    (comp (ref "R63")
      (value "12.1K")
      (footprint "eagle-import:R0603")
      (libsource (lib "eagle-import") (part "R-US_R0603"))
    )
    (comp (ref "R64")
      (value "1M")
      (footprint "eagle-import:R0603")
      (libsource (lib "eagle-import") (part "R-US_R0603"))
    )
    (comp (ref "R65")
      (value "5.6K")
      (footprint "eagle-import:R0603")
      (libsource (lib "eagle-import") (part "R-US_R0603"))
    )
    (comp (ref "R66")
      (value "5.6K")
      (footprint "eagle-import:R0603")
      (libsource (lib "eagle-import") (part "R-US_R0603"))
    )
    (comp (ref "R67")
      (value "5.6K")
      (footprint "eagle-import:R0603")
      (libsource (lib "eagle-import") (part "R-US_R0603"))
    )
    (comp (ref "R68")
      (value "5.6K")
      (footprint "eagle-import:R0603")
      (libsource (lib "eagle-import") (part "R-US_R0603"))
    )
    (comp (ref "R69")
      (value "22R")
      (footprint "eagle-import:R0603")
      (libsource (lib "eagle-import") (part "R-US_R0603"))
    )
    (comp (ref "R70")
      (value "22R")
      (footprint "eagle-import:R0603")
      (libsource (lib "eagle-import") (part "R-US_R0603"))
    )
    (comp (ref "R71")
      (value "10k")
      (footprint "eagle-import:R0603")
      (libsource (lib "eagle-import") (part "R-US_R0603"))
    )
    (comp (ref "R72")
      (value "10k")
      (footprint "eagle-import:R0603")
      (libsource (lib "eagle-import") (part "R-US_R0603"))
    )
    (comp (ref "R73")
      (value "22R")
      (footprint "eagle-import:R0603")
      (libsource (lib "eagle-import") (part "R-US_R0603"))
    )
    (comp (ref "R74")
      (value "10k")
      (footprint "eagle-import:R0603")
      (libsource (lib "eagle-import") (part "R-US_R0603"))
    )
    (comp (ref "R75")
      (value "22R")
      (footprint "eagle-import:R0603")
      (libsource (lib "eagle-import") (part "R-US_R0603"))
    )
    (comp (ref "R76")
      (value "10k")
      (footprint "eagle-import:R0603")
      (libsource (lib "eagle-import") (part "R-US_R0603"))
    )
    (comp (ref "R77")
      (value "1k")
      (footprint "eagle-import:R0603")
      (libsource (lib "eagle-import") (part "R-US_R0603"))
    )
    (comp (ref "R78")
      (value "2.2K")
      (footprint "eagle-import:R0603")
      (libsource (lib "eagle-import") (part "R-US_R0603"))
    )
    (comp (ref "RJ1")
      (value "HR911105A")
      (footprint "eagle-import:HR911105A")
      (libsource (lib "eagle-import") (part "HR911105A"))
    )
    (comp (ref "U$1")
      (value "ETH1506S")
      (footprint "eagle-import:TO263AB")
      (libsource (lib "eagle-import") (part "ETH1506S"))
    )
    (comp (ref "U$2")
      (value "TC4427")
      (footprint "eagle-import:SOIC8")
      (libsource (lib "eagle-import") (part "TC4427"))
    )
    (comp (ref "X5")
      (value "180G-2")
      (footprint "eagle-import:180G-2")
      (libsource (lib "eagle-import") (part "180G-2"))
    )
    (comp (ref "X6")
      (value "180G-2")
      (footprint "eagle-import:180G-2")
      (libsource (lib "eagle-import") (part "180G-2"))
    )
    (comp (ref "X7")
      (value "180G-2")
      (footprint "eagle-import:180G-2")
      (libsource (lib "eagle-import") (part "180G-2"))
    )
    (comp (ref "X8")
      (value "180G-2")
      (footprint "eagle-import:180G-2")
      (libsource (lib "eagle-import") (part "180G-2"))
    )
    (comp (ref "X9")
      (value "180G-2")
      (footprint "eagle-import:180G-2")
      (libsource (lib "eagle-import") (part "180G-2"))
    )
    (comp (ref "X10")
      (value "180G-2")
      (footprint "eagle-import:180G-2")
      (libsource (lib "eagle-import") (part "180G-2"))
    )
    (comp (ref "X11")
      (value "180G-2")
      (footprint "eagle-import:180G-2")
      (libsource (lib "eagle-import") (part "180G-2"))
    )
    (comp (ref "X12")
      (value "180G-2")
      (footprint "eagle-import:180G-2")
      (libsource (lib "eagle-import") (part "180G-2"))
    )
  )
  (nets
    (net (code "1") (name "+5V") (class "Default")
      (node (ref "D2") (pin "A") (pinfunction "A_A") (pintype "passive"))
      (node (ref "POWER") (pin "P$4") (pinfunction "+5V_P$4") (pintype "power_in"))
      (node (ref "X12") (pin "1") (pinfunction "1_1") (pintype "passive"))
    )
    (net (code "2") (name "3.3V") (class "Default")
      (node (ref "C1") (pin "2") (pinfunction "2_2") (pintype "passive"))
      (node (ref "C10") (pin "2") (pinfunction "2_2") (pintype "passive"))
      (node (ref "C11") (pin "2") (pinfunction "2_2") (pintype "passive"))
      (node (ref "C12") (pin "2") (pinfunction "2_2") (pintype "passive"))
      (node (ref "C13") (pin "2") (pinfunction "2_2") (pintype "passive"))
      (node (ref "C14") (pin "2") (pinfunction "2_2") (pintype "passive"))
      (node (ref "C25") (pin "1") (pinfunction "1_1") (pintype "passive"))
      (node (ref "C28") (pin "1") (pinfunction "1_1") (pintype "passive"))
      (node (ref "C31") (pin "2") (pinfunction "2_2") (pintype "passive"))
      (node (ref "C38") (pin "1") (pinfunction "1_1") (pintype "passive"))
      (node (ref "C41") (pin "1") (pinfunction "1_1") (pintype "passive"))
      (node (ref "C44") (pin "1") (pinfunction "1_1") (pintype "passive"))
      (node (ref "C50") (pin "A") (pinfunction "+_A") (pintype "passive"))
      (node (ref "C51") (pin "1") (pinfunction "1_1") (pintype "passive"))
      (node (ref "C65") (pin "1") (pinfunction "1_1") (pintype "passive"))
      (node (ref "C7") (pin "A") (pinfunction "+_A") (pintype "passive"))
      (node (ref "C8") (pin "2") (pinfunction "2_2") (pintype "passive"))
      (node (ref "C9") (pin "2") (pinfunction "2_2") (pintype "passive"))
      (node (ref "FB1") (pin "1") (pinfunction "P$1_1") (pintype "bidirectional"))
      (node (ref "IC1") (pin "19") (pinfunction "VBAT_19") (pintype "bidirectional"))
      (node (ref "IC1") (pin "28") (pinfunction "VDD(3V3)1_28") (pintype "bidirectional"))
      (node (ref "IC1") (pin "42") (pinfunction "VDD(REG)(3V3)1_42") (pintype "bidirectional"))
      (node (ref "IC1") (pin "54") (pinfunction "VDD(3V3)2_54") (pintype "bidirectional"))
      (node (ref "IC1") (pin "71") (pinfunction "VDD(3V3)3_71") (pintype "bidirectional"))
      (node (ref "IC1") (pin "84") (pinfunction "VDD(REG)(3V3)2_84") (pintype "bidirectional"))
      (node (ref "IC1") (pin "96") (pinfunction "VDD(3V3)4_96") (pintype "bidirectional"))
      (node (ref "IC10") (pin "2") (pinfunction "OUT_2") (pintype "output"))
      (node (ref "IC10") (pin "4") (pinfunction "OUT_4") (pintype "output"))
      (node (ref "IC2") (pin "P10") (pinfunction "VDD_P10") (pintype "bidirectional"))
      (node (ref "IC3") (pin "P10") (pinfunction "VDD_P10") (pintype "bidirectional"))
      (node (ref "IC4") (pin "17") (pinfunction "VDD_17") (pintype "bidirectional"))
      (node (ref "IC5") (pin "P10") (pinfunction "VDD_P10") (pintype "bidirectional"))
      (node (ref "IC6") (pin "P10") (pinfunction "VDD_P10") (pintype "bidirectional"))
      (node (ref "IC7") (pin "5") (pinfunction "VCC_5") (pintype "power_in"))
      (node (ref "IC8") (pin "9") (pinfunction "VDDIO_9") (pintype "bidirectional"))
      (node (ref "JP1") (pin "1") (pinfunction "1_1") (pintype "passive"))
      (node (ref "JP14") (pin "1") (pinfunction "1_1") (pintype "passive"))
      (node (ref "JP16") (pin "1") (pinfunction "1_1") (pintype "passive"))
      (node (ref "JP17") (pin "2") (pinfunction "2_2") (pintype "passive"))
      (node (ref "JP19") (pin "1") (pinfunction "1_1") (pintype "passive"))
      (node (ref "JP2") (pin "1") (pinfunction "1_1") (pintype "passive"))
      (node (ref "JP21") (pin "1") (pinfunction "1_1") (pintype "passive"))
      (node (ref "JP22") (pin "1") (pinfunction "1_1") (pintype "passive"))
      (node (ref "JP26") (pin "1") (pinfunction "1_1") (pintype "passive"))
      (node (ref "JP30") (pin "2") (pinfunction "2_2") (pintype "passive"))
      (node (ref "JP31") (pin "1") (pinfunction "1_1") (pintype "passive"))
      (node (ref "JP4") (pin "1") (pinfunction "1_1") (pintype "passive"))
      (node (ref "L1") (pin "2") (pinfunction "2_2") (pintype "passive"))
      (node (ref "Q1") (pin "E") (pinfunction "E_E") (pintype "passive"))
      (node (ref "R1") (pin "2") (pinfunction "2_2") (pintype "passive"))
      (node (ref "R14") (pin "2") (pinfunction "2_2") (pintype "passive"))
      (node (ref "R15") (pin "2") (pinfunction "2_2") (pintype "passive"))
      (node (ref "R16") (pin "2") (pinfunction "2_2") (pintype "passive"))
      (node (ref "R17") (pin "1") (pinfunction "1_1") (pintype "passive"))
      (node (ref "R2") (pin "2") (pinfunction "2_2") (pintype "passive"))
      (node (ref "R22") (pin "1") (pinfunction "1_1") (pintype "passive"))
      (node (ref "R23") (pin "2") (pinfunction "2_2") (pintype "passive"))
      (node (ref "R24") (pin "2") (pinfunction "2_2") (pintype "passive"))
      (node (ref "R25") (pin "2") (pinfunction "2_2") (pintype "passive"))
      (node (ref "R28") (pin "2") (pinfunction "2_2") (pintype "passive"))
      (node (ref "R29") (pin "2") (pinfunction "2_2") (pintype "passive"))
      (node (ref "R3") (pin "2") (pinfunction "2_2") (pintype "passive"))
      (node (ref "R30") (pin "2") (pinfunction "2_2") (pintype "passive"))
      (node (ref "R35") (pin "2") (pinfunction "2_2") (pintype "passive"))
      (node (ref "R36") (pin "2") (pinfunction "2_2") (pintype "passive"))
      (node (ref "R37") (pin "2") (pinfunction "2_2") (pintype "passive"))
      (node (ref "R38") (pin "2") (pinfunction "2_2") (pintype "passive"))
      (node (ref "R39") (pin "2") (pinfunction "2_2") (pintype "passive"))
      (node (ref "R41") (pin "2") (pinfunction "2_2") (pintype "passive"))
      (node (ref "R42") (pin "2") (pinfunction "2_2") (pintype "passive"))
      (node (ref "R44") (pin "2") (pinfunction "2_2") (pintype "passive"))
      (node (ref "R45") (pin "2") (pinfunction "2_2") (pintype "passive"))
      (node (ref "R5") (pin "2") (pinfunction "2_2") (pintype "passive"))
      (node (ref "R52") (pin "2") (pinfunction "2_2") (pintype "passive"))
      (node (ref "R53") (pin "2") (pinfunction "2_2") (pintype "passive"))
      (node (ref "R6") (pin "2") (pinfunction "2_2") (pintype "passive"))
      (node (ref "R77") (pin "2") (pinfunction "2_2") (pintype "passive"))
      (node (ref "RN1") (pin "1") (pinfunction "1_1") (pintype "passive"))
      (node (ref "RN1") (pin "2") (pinfunction "1_2") (pintype "passive"))
      (node (ref "RN1") (pin "3") (pinfunction "1_3") (pintype "passive"))
      (node (ref "RN1") (pin "4") (pinfunction "1_4") (pintype "passive"))
      (node (ref "U1") (pin "4") (pinfunction "VCC_4") (pintype "bidirectional"))
    )
    (net (code "3") (name "5V") (class "Default")
      (node (ref "C64") (pin "A") (pinfunction "+_A") (pintype "passive"))
      (node (ref "D1") (pin "C") (pinfunction "C_C") (pintype "passive"))
      (node (ref "D2") (pin "C") (pinfunction "C_C") (pintype "passive"))
      (node (ref "IC10") (pin "3") (pinfunction "IN_3") (pintype "input"))
      (node (ref "JP5") (pin "3") (pinfunction "3_3") (pintype "passive"))
    )
    (net (code "4") (name "CTS") (class "Default")
      (node (ref "JP5") (pin "2") (pinfunction "2_2") (pintype "passive"))
    )
    (net (code "5") (name "DIR1") (class "Default")
      (node (ref "IC1") (pin "80") (pinfunction "P0[5]/I2SRX_WS/TD2/CAP2[1]_80") (pintype "bidirectional"))
      (node (ref "IC2") (pin "P14") (pinfunction "DIR_P14") (pintype "bidirectional"))
      (node (ref "JP7") (pin "2") (pinfunction "2_2") (pintype "passive"))
    )
    (net (code "6") (name "DIR2") (class "Default")
      (node (ref "IC1") (pin "49") (pinfunction "P0[11]/RXD2/SCL2/MAT3[1]_49") (pintype "bidirectional"))
      (node (ref "IC3") (pin "P14") (pinfunction "DIR_P14") (pintype "bidirectional"))
      (node (ref "JP9") (pin "2") (pinfunction "2_2") (pintype "passive"))
    )
    (net (code "7") (name "DIR3") (class "Default")
      (node (ref "IC1") (pin "58") (pinfunction "P0[20]/DTR1/SCL1_58") (pintype "bidirectional"))
      (node (ref "IC5") (pin "P14") (pinfunction "DIR_P14") (pintype "bidirectional"))
      (node (ref "JP12") (pin "2") (pinfunction "2_2") (pintype "passive"))
    )
    (net (code "8") (name "DIR4") (class "Default")
      (node (ref "IC1") (pin "56") (pinfunction "P0[22]/RTS1/TD1_56") (pintype "bidirectional"))
      (node (ref "IC6") (pin "P14") (pinfunction "DIR_P14") (pintype "bidirectional"))
      (node (ref "JP15") (pin "2") (pinfunction "2_2") (pintype "passive"))
    )
    (net (code "9") (name "EN1") (class "Default")
      (node (ref "IC1") (pin "81") (pinfunction "P0[4]/I2SRX_CLK/RD2/CAP2[0]_81") (pintype "bidirectional"))
      (node (ref "IC2") (pin "P23") (pinfunction "^EN_P23") (pintype "bidirectional"))
      (node (ref "JP7") (pin "1") (pinfunction "1_1") (pintype "passive"))
    )
    (net (code "10") (name "EN2") (class "Default")
      (node (ref "IC1") (pin "48") (pinfunction "P0[10]/TXD2/SDA2/MAT3[0]_48") (pintype "bidirectional"))
      (node (ref "IC3") (pin "P23") (pinfunction "^EN_P23") (pintype "bidirectional"))
      (node (ref "JP9") (pin "1") (pinfunction "1_1") (pintype "passive"))
    )
    (net (code "11") (name "EN3") (class "Default")
      (node (ref "IC1") (pin "59") (pinfunction "P0[19]/DSR1/SDA1_59") (pintype "bidirectional"))
      (node (ref "IC5") (pin "P23") (pinfunction "^EN_P23") (pintype "bidirectional"))
      (node (ref "JP12") (pin "1") (pinfunction "1_1") (pintype "passive"))
    )
    (net (code "12") (name "EN4") (class "Default")
      (node (ref "IC1") (pin "57") (pinfunction "P0[21]/RI1/RD1_57") (pintype "bidirectional"))
      (node (ref "IC6") (pin "P23") (pinfunction "^EN_P23") (pintype "bidirectional"))
      (node (ref "JP15") (pin "1") (pinfunction "1_1") (pintype "passive"))
    )
    (net (code "13") (name "ENET_CRS") (class "Default")
      (node (ref "IC1") (pin "92") (pinfunction "P1[8]/ENET_CRS_92") (pintype "bidirectional"))
      (node (ref "R60") (pin "2") (pinfunction "2_2") (pintype "passive"))
    )
    (net (code "14") (name "ENET_MDC") (class "Default")
      (node (ref "IC1") (pin "87") (pinfunction "P1[16]/ENET_MDC_87") (pintype "bidirectional"))
      (node (ref "IC8") (pin "13") (pinfunction "MDC_13") (pintype "bidirectional"))
    )
    (net (code "15") (name "ENET_MDIO") (class "Default")
      (node (ref "IC1") (pin "86") (pinfunction "P1[17]/ENET_MDIO_86") (pintype "bidirectional"))
      (node (ref "IC8") (pin "12") (pinfunction "MDIO_12") (pintype "bidirectional"))
      (node (ref "R52") (pin "1") (pinfunction "1_1") (pintype "passive"))
    )
    (net (code "16") (name "ENET_REF_CLK") (class "Default")
      (node (ref "IC1") (pin "88") (pinfunction "P1[15]/ENET_REF_CLK_88") (pintype "bidirectional"))
      (node (ref "R51") (pin "2") (pinfunction "2_2") (pintype "passive"))
    )
    (net (code "17") (name "ENET_RXD0") (class "Default")
      (node (ref "IC1") (pin "91") (pinfunction "P1[9]/ENET_RXD0_91") (pintype "bidirectional"))
      (node (ref "R58") (pin "2") (pinfunction "2_2") (pintype "passive"))
    )
    (net (code "18") (name "ENET_RXD1") (class "Default")
      (node (ref "IC1") (pin "90") (pinfunction "P1[10]/ENET_RXD1_90") (pintype "bidirectional"))
      (node (ref "R59") (pin "2") (pinfunction "2_2") (pintype "passive"))
    )
    (net (code "19") (name "ENET_RX_ER") (class "Default")
      (node (ref "IC1") (pin "89") (pinfunction "P1[14]/ENET_RX_ER_89") (pintype "bidirectional"))
      (node (ref "IC8") (pin "10") (pinfunction "RXER_10") (pintype "bidirectional"))
      (node (ref "R53") (pin "1") (pinfunction "1_1") (pintype "passive"))
    )
    (net (code "20") (name "ENET_TXD0") (class "Default")
      (node (ref "IC1") (pin "95") (pinfunction "P1[0]/ENET_TXD0_95") (pintype "bidirectional"))
      (node (ref "IC8") (pin "17") (pinfunction "TXD0_17") (pintype "bidirectional"))
    )
    (net (code "21") (name "ENET_TXD1") (class "Default")
      (node (ref "IC1") (pin "94") (pinfunction "P1[1]/ENET_TXD1_94") (pintype "bidirectional"))
      (node (ref "IC8") (pin "18") (pinfunction "TXD1_18") (pintype "bidirectional"))
    )
    (net (code "22") (name "ENET_TX_EN") (class "Default")
      (node (ref "IC1") (pin "93") (pinfunction "P1[4]/ENET_TX_EN_93") (pintype "bidirectional"))
      (node (ref "IC8") (pin "16") (pinfunction "TXEN_16") (pintype "bidirectional"))
    )
    (net (code "23") (name "GND") (class "Default")
      (node (ref "C1") (pin "1") (pinfunction "1_1") (pintype "passive"))
      (node (ref "C10") (pin "1") (pinfunction "1_1") (pintype "passive"))
      (node (ref "C11") (pin "1") (pinfunction "1_1") (pintype "passive"))
      (node (ref "C12") (pin "1") (pinfunction "1_1") (pintype "passive"))
      (node (ref "C13") (pin "1") (pinfunction "1_1") (pintype "passive"))
      (node (ref "C14") (pin "1") (pinfunction "1_1") (pintype "passive"))
      (node (ref "C15") (pin "1") (pinfunction "1_1") (pintype "passive"))
      (node (ref "C16") (pin "1") (pinfunction "1_1") (pintype "passive"))
      (node (ref "C2") (pin "2") (pinfunction "2_2") (pintype "passive"))
      (node (ref "C21") (pin "C") (pinfunction "-_C") (pintype "passive"))
      (node (ref "C22") (pin "C") (pinfunction "-_C") (pintype "passive"))
      (node (ref "C23") (pin "C") (pinfunction "-_C") (pintype "passive"))
      (node (ref "C24") (pin "C") (pinfunction "-_C") (pintype "passive"))
      (node (ref "C25") (pin "2") (pinfunction "2_2") (pintype "passive"))
      (node (ref "C26") (pin "-") (pinfunction "-_-") (pintype "passive"))
      (node (ref "C27") (pin "2") (pinfunction "2_2") (pintype "passive"))
      (node (ref "C28") (pin "2") (pinfunction "2_2") (pintype "passive"))
      (node (ref "C29") (pin "-") (pinfunction "-_-") (pintype "passive"))
      (node (ref "C3") (pin "2") (pinfunction "2_2") (pintype "passive"))
      (node (ref "C30") (pin "2") (pinfunction "2_2") (pintype "passive"))
      (node (ref "C31") (pin "1") (pinfunction "1_1") (pintype "passive"))
      (node (ref "C32") (pin "1") (pinfunction "1_1") (pintype "passive"))
      (node (ref "C33") (pin "1") (pinfunction "1_1") (pintype "passive"))
      (node (ref "C38") (pin "2") (pinfunction "2_2") (pintype "passive"))
      (node (ref "C39") (pin "-") (pinfunction "-_-") (pintype "passive"))
      (node (ref "C4") (pin "1") (pinfunction "1_1") (pintype "passive"))
      (node (ref "C40") (pin "2") (pinfunction "2_2") (pintype "passive"))
      (node (ref "C41") (pin "2") (pinfunction "2_2") (pintype "passive"))
      (node (ref "C42") (pin "-") (pinfunction "-_-") (pintype "passive"))
      (node (ref "C43") (pin "2") (pinfunction "2_2") (pintype "passive"))
      (node (ref "C44") (pin "2") (pinfunction "2_2") (pintype "passive"))
      (node (ref "C45") (pin "C") (pinfunction "-_C") (pintype "passive"))
      (node (ref "C46") (pin "2") (pinfunction "2_2") (pintype "passive"))
      (node (ref "C47") (pin "2") (pinfunction "2_2") (pintype "passive"))
      (node (ref "C48") (pin "C") (pinfunction "-_C") (pintype "passive"))
      (node (ref "C49") (pin "2") (pinfunction "2_2") (pintype "passive"))
      (node (ref "C5") (pin "1") (pinfunction "1_1") (pintype "passive"))
      (node (ref "C50") (pin "C") (pinfunction "-_C") (pintype "passive"))
      (node (ref "C51") (pin "2") (pinfunction "2_2") (pintype "passive"))
      (node (ref "C52") (pin "2") (pinfunction "2_2") (pintype "passive"))
      (node (ref "C53") (pin "2") (pinfunction "2_2") (pintype "passive"))
      (node (ref "C54") (pin "2") (pinfunction "2_2") (pintype "passive"))
      (node (ref "C55") (pin "2") (pinfunction "2_2") (pintype "passive"))
      (node (ref "C56") (pin "2") (pinfunction "2_2") (pintype "passive"))
      (node (ref "C57") (pin "2") (pinfunction "2_2") (pintype "passive"))
      (node (ref "C58") (pin "2") (pinfunction "2_2") (pintype "passive"))
      (node (ref "C59") (pin "2") (pinfunction "2_2") (pintype "passive"))
      (node (ref "C6") (pin "2") (pinfunction "2_2") (pintype "passive"))
      (node (ref "C60") (pin "-") (pinfunction "-_-") (pintype "passive"))
      (node (ref "C61") (pin "C") (pinfunction "-_C") (pintype "passive"))
      (node (ref "C62") (pin "2") (pinfunction "2_2") (pintype "passive"))
      (node (ref "C63") (pin "-") (pinfunction "-_-") (pintype "passive"))
      (node (ref "C64") (pin "C") (pinfunction "-_C") (pintype "passive"))
      (node (ref "C65") (pin "2") (pinfunction "2_2") (pintype "passive"))
      (node (ref "C66") (pin "2") (pinfunction "2_2") (pintype "passive"))
      (node (ref "C7") (pin "C") (pinfunction "-_C") (pintype "passive"))
      (node (ref "C8") (pin "1") (pinfunction "1_1") (pintype "passive"))
      (node (ref "C9") (pin "1") (pinfunction "1_1") (pintype "passive"))
      (node (ref "CN1") (pin "GND") (pinfunction "GND_GND") (pintype "power_in"))
      (node (ref "IC1") (pin "11") (pinfunction "VSSA_11") (pintype "bidirectional"))
      (node (ref "IC1") (pin "15") (pinfunction "VREFN_15") (pintype "bidirectional"))
      (node (ref "IC1") (pin "31") (pinfunction "VSS1_31") (pintype "bidirectional"))
      (node (ref "IC1") (pin "41") (pinfunction "VSS2_41") (pintype "bidirectional"))
      (node (ref "IC1") (pin "55") (pinfunction "VSS3_55") (pintype "bidirectional"))
      (node (ref "IC1") (pin "72") (pinfunction "VSS4_72") (pintype "bidirectional"))
      (node (ref "IC1") (pin "83") (pinfunction "VSS6_83") (pintype "bidirectional"))
      (node (ref "IC1") (pin "97") (pinfunction "VSS5_97") (pintype "bidirectional"))
      (node (ref "IC10") (pin "1") (pinfunction "ADJ_1") (pintype "input"))
      (node (ref "IC2") (pin "EPAD") (pinfunction "PAD_EPAD") (pintype "bidirectional"))
      (node (ref "IC2") (pin "P13") (pinfunction "GND1_P13") (pintype "bidirectional"))
      (node (ref "IC2") (pin "P24") (pinfunction "GND2_P24") (pintype "bidirectional"))
      (node (ref "IC3") (pin "EPAD") (pinfunction "PAD_EPAD") (pintype "bidirectional"))
      (node (ref "IC3") (pin "P13") (pinfunction "GND1_P13") (pintype "bidirectional"))
      (node (ref "IC3") (pin "P24") (pinfunction "GND2_P24") (pintype "bidirectional"))
      (node (ref "IC4") (pin "13") (pinfunction "P0B_13") (pintype "bidirectional"))
      (node (ref "IC4") (pin "16") (pinfunction "A1_16") (pintype "bidirectional"))
      (node (ref "IC4") (pin "18") (pinfunction "P2B_18") (pintype "bidirectional"))
      (node (ref "IC4") (pin "3") (pinfunction "P3B_3") (pintype "bidirectional"))
      (node (ref "IC4") (pin "4") (pinfunction "HVC/A0_4") (pintype "bidirectional"))
      (node (ref "IC4") (pin "7") (pinfunction "VSS_7") (pintype "bidirectional"))
      (node (ref "IC4") (pin "8") (pinfunction "P1B_8") (pintype "bidirectional"))
      (node (ref "IC5") (pin "EPAD") (pinfunction "PAD_EPAD") (pintype "bidirectional"))
      (node (ref "IC5") (pin "P13") (pinfunction "GND1_P13") (pintype "bidirectional"))
      (node (ref "IC5") (pin "P24") (pinfunction "GND2_P24") (pintype "bidirectional"))
      (node (ref "IC6") (pin "EPAD") (pinfunction "PAD_EPAD") (pintype "bidirectional"))
      (node (ref "IC6") (pin "P13") (pinfunction "GND1_P13") (pintype "bidirectional"))
      (node (ref "IC6") (pin "P24") (pinfunction "GND2_P24") (pintype "bidirectional"))
      (node (ref "IC7") (pin "3") (pinfunction "GND_3") (pintype "power_in"))
      (node (ref "IC8") (pin "THERM") (pinfunction "GND_THERM") (pintype "bidirectional"))
      (node (ref "IC9") (pin "2") (pinfunction "GND_2") (pintype "passive"))
      (node (ref "J10") (pin "VIN0") (pinfunction "PWR_VIN0") (pintype "bidirectional"))
      (node (ref "J5") (pin "VIN0") (pinfunction "PWR_VIN0") (pintype "bidirectional"))
      (node (ref "JP1") (pin "2") (pinfunction "2_2") (pintype "passive"))
      (node (ref "JP10") (pin "1") (pinfunction "1_1") (pintype "passive"))
      (node (ref "JP10") (pin "2") (pinfunction "2_2") (pintype "passive"))
      (node (ref "JP10") (pin "3") (pinfunction "3_3") (pintype "passive"))
      (node (ref "JP10") (pin "4") (pinfunction "4_4") (pintype "passive"))
      (node (ref "JP12") (pin "4") (pinfunction "4_4") (pintype "passive"))
      (node (ref "JP14") (pin "2") (pinfunction "2_2") (pintype "passive"))
      (node (ref "JP15") (pin "4") (pinfunction "4_4") (pintype "passive"))
      (node (ref "JP16") (pin "2") (pinfunction "2_2") (pintype "passive"))
      (node (ref "JP17") (pin "3") (pinfunction "3_3") (pintype "passive"))
      (node (ref "JP19") (pin "2") (pinfunction "2_2") (pintype "passive"))
      (node (ref "JP21") (pin "2") (pinfunction "2_2") (pintype "passive"))
      (node (ref "JP22") (pin "2") (pinfunction "2_2") (pintype "passive"))
      (node (ref "JP23") (pin "2") (pinfunction "2_2") (pintype "passive"))
      (node (ref "JP26") (pin "2") (pinfunction "2_2") (pintype "passive"))
      (node (ref "JP3") (pin "3") (pinfunction "3_3") (pintype "passive"))
      (node (ref "JP5") (pin "1") (pinfunction "1_1") (pintype "passive"))
      (node (ref "JP6") (pin "3") (pinfunction "3_3") (pintype "passive"))
      (node (ref "JP7") (pin "4") (pinfunction "4_4") (pintype "passive"))
      (node (ref "JP9") (pin "4") (pinfunction "4_4") (pintype "passive"))
      (node (ref "LED1") (pin "C") (pinfunction "C_C") (pintype "passive"))
      (node (ref "LED10") (pin "C") (pinfunction "C_C") (pintype "passive"))
      (node (ref "LED2") (pin "C") (pinfunction "C_C") (pintype "passive"))
      (node (ref "LED3") (pin "C") (pinfunction "C_C") (pintype "passive"))
      (node (ref "LED4") (pin "C") (pinfunction "C_C") (pintype "passive"))
      (node (ref "LED9") (pin "C") (pinfunction "C_C") (pintype "passive"))
      (node (ref "POWER") (pin "P$2") (pinfunction "GND_P$2") (pintype "power_in"))
      (node (ref "POWER") (pin "P$3") (pinfunction "GND1_P$3") (pintype "power_in"))
      (node (ref "Q6") (pin "S") (pinfunction "S_S") (pintype "passive"))
      (node (ref "Q7") (pin "S") (pinfunction "S_S") (pintype "passive"))
      (node (ref "Q8") (pin "3") (pinfunction "S_3") (pintype "passive"))
      (node (ref "Q9") (pin "3") (pinfunction "S_3") (pintype "passive"))
      (node (ref "R26") (pin "2") (pinfunction "2_2") (pintype "passive"))
      (node (ref "R27") (pin "2") (pinfunction "2_2") (pintype "passive"))
      (node (ref "R31") (pin "1") (pinfunction "1_1") (pintype "passive"))
      (node (ref "R32") (pin "1") (pinfunction "1_1") (pintype "passive"))
      (node (ref "R33") (pin "1") (pinfunction "1_1") (pintype "passive"))
      (node (ref "R34") (pin "1") (pinfunction "1_1") (pintype "passive"))
      (node (ref "R40") (pin "2") (pinfunction "2_2") (pintype "passive"))
      (node (ref "R43") (pin "2") (pinfunction "2_2") (pintype "passive"))
      (node (ref "R46") (pin "1") (pinfunction "1_1") (pintype "passive"))
      (node (ref "R47") (pin "1") (pinfunction "1_1") (pintype "passive"))
      (node (ref "R48") (pin "1") (pinfunction "1_1") (pintype "passive"))
      (node (ref "R49") (pin "1") (pinfunction "1_1") (pintype "passive"))
      (node (ref "R50") (pin "1") (pinfunction "1_1") (pintype "passive"))
      (node (ref "R61") (pin "1") (pinfunction "1_1") (pintype "passive"))
      (node (ref "R62") (pin "1") (pinfunction "1_1") (pintype "passive"))
      (node (ref "R63") (pin "1") (pinfunction "1_1") (pintype "passive"))
      (node (ref "R71") (pin "1") (pinfunction "1_1") (pintype "passive"))
      (node (ref "R72") (pin "1") (pinfunction "1_1") (pintype "passive"))
      (node (ref "R74") (pin "2") (pinfunction "2_2") (pintype "passive"))
      (node (ref "R76") (pin "2") (pinfunction "2_2") (pintype "passive"))
      (node (ref "RJ1") (pin "GND") (pinfunction "GND_GND") (pintype "bidirectional"))
      (node (ref "RJ1") (pin "SHIELD0") (pinfunction "SHIELD0_SHIELD0") (pintype "bidirectional"))
      (node (ref "RJ1") (pin "SHIELD1") (pinfunction "SHIELD1_SHIELD1") (pintype "bidirectional"))
      (node (ref "S1") (pin "3") (pinfunction "3_3") (pintype "passive"))
      (node (ref "S1") (pin "4") (pinfunction "4_4") (pintype "passive"))
      (node (ref "S2") (pin "3") (pinfunction "3_3") (pintype "passive"))
      (node (ref "S2") (pin "4") (pinfunction "4_4") (pintype "passive"))
      (node (ref "S3") (pin "2") (pinfunction "2_2") (pintype "passive"))
      (node (ref "SL1") (pin "1") (pinfunction "1_1") (pintype "passive"))
      (node (ref "SL1") (pin "3") (pinfunction "3_3") (pintype "passive"))
      (node (ref "SL1") (pin "5") (pinfunction "5_5") (pintype "passive"))
      (node (ref "SL1") (pin "7") (pinfunction "7_7") (pintype "passive"))
      (node (ref "U$2") (pin "3") (pinfunction "P$2_3") (pintype "bidirectional"))
      (node (ref "U1") (pin "6") (pinfunction "GND_6") (pintype "bidirectional"))
      (node (ref "U1") (pin "CD2") (pinfunction "SHIELD_CD2") (pintype "bidirectional"))
      (node (ref "U1") (pin "GND1") (pinfunction "SHIELD_GND1") (pintype "bidirectional"))
      (node (ref "X11") (pin "2") (pinfunction "2_2") (pintype "passive"))
      (node (ref "X12") (pin "2") (pinfunction "2_2") (pintype "passive"))
      (node (ref "X5") (pin "2") (pinfunction "2_2") (pintype "passive"))
      (node (ref "X6") (pin "2") (pinfunction "2_2") (pintype "passive"))
    )
    (net (code "24") (name "GPIO_FET") (class "Default")
      (node (ref "Q7") (pin "G") (pinfunction "G_G") (pintype "passive"))
      (node (ref "R70") (pin "2") (pinfunction "2_2") (pintype "passive"))
    )
    (net (code "25") (name "ISP_BOOT") (class "Default")
      (node (ref "IC1") (pin "53") (pinfunction "P2[10]/EINT0/NMI_53") (pintype "bidirectional"))
      (node (ref "JP25") (pin "2") (pinfunction "2_2") (pintype "passive"))
      (node (ref "R15") (pin "1") (pinfunction "1_1") (pintype "passive"))
      (node (ref "S2") (pin "1") (pinfunction "1_1") (pintype "passive"))
      (node (ref "S2") (pin "2") (pinfunction "2_2") (pintype "passive"))
    )
    (net (code "26") (name "JTAG-RTCK") (class "Default")
      (node (ref "IC1") (pin "100") (pinfunction "RTCK_100") (pintype "bidirectional"))
    )
    (net (code "27") (name "JTAG-TCK") (class "Default")
      (node (ref "IC1") (pin "5") (pinfunction "TCK/SWDCLK_5") (pintype "bidirectional"))
    )
    (net (code "28") (name "JTAG-TDI") (class "Default")
      (node (ref "IC1") (pin "2") (pinfunction "TDI_2") (pintype "bidirectional"))
    )
    (net (code "29") (name "JTAG-TDO") (class "Default")
      (node (ref "IC1") (pin "1") (pinfunction "TDO/SWO_1") (pintype "bidirectional"))
    )
    (net (code "30") (name "JTAG-TMS") (class "Default")
      (node (ref "IC1") (pin "3") (pinfunction "TMS/SWDIO_3") (pintype "bidirectional"))
    )
    (net (code "31") (name "JTAG-TRST") (class "Default")
      (node (ref "IC1") (pin "4") (pinfunction "TRST_4") (pintype "bidirectional"))
    )
    (net (code "32") (name "LED1") (class "Default")
      (node (ref "IC1") (pin "32") (pinfunction "P1[18]/USB_UP_LED/PWM1[1]/CAP1[0]_32") (pintype "bidirectional"))
      (node (ref "JP29") (pin "1") (pinfunction "1_1") (pintype "passive"))
      (node (ref "R10") (pin "2") (pinfunction "2_2") (pintype "passive"))
    )
    (net (code "33") (name "LED1{slash}REGOFF") (class "Default")
      (node (ref "IC8") (pin "3") (pinfunction "LED1/REGOFF_3") (pintype "bidirectional"))
      (node (ref "RJ1") (pin "G+") (pinfunction "G+_G+") (pintype "bidirectional"))
    )
    (net (code "34") (name "LED2") (class "Default")
      (node (ref "IC1") (pin "33") (pinfunction "P1[19]/MC0A/USB_PPWR/CAP1[1]_33") (pintype "bidirectional"))
      (node (ref "JP29") (pin "2") (pinfunction "2_2") (pintype "passive"))
      (node (ref "R11") (pin "2") (pinfunction "2_2") (pintype "passive"))
    )
    (net (code "35") (name "LED2{slash}NINTSEL") (class "Default")
      (node (ref "IC8") (pin "2") (pinfunction "LED2/NINTSEL_2") (pintype "bidirectional"))
      (node (ref "R62") (pin "2") (pinfunction "2_2") (pintype "passive"))
      (node (ref "RJ1") (pin "Y+") (pinfunction "Y+_Y+") (pintype "bidirectional"))
    )
    (net (code "36") (name "LED3") (class "Default")
      (node (ref "IC1") (pin "34") (pinfunction "P1[20]/MCFB0/PWM1[2]/SCK0_34") (pintype "bidirectional"))
      (node (ref "JP29") (pin "3") (pinfunction "3_3") (pintype "passive"))
      (node (ref "R12") (pin "2") (pinfunction "2_2") (pintype "passive"))
    )
    (net (code "37") (name "LED4") (class "Default")
      (node (ref "IC1") (pin "35") (pinfunction "P1[21]/MCABORT/PWM1[3]/SSEL0_35") (pintype "bidirectional"))
      (node (ref "JP29") (pin "4") (pinfunction "4_4") (pintype "passive"))
      (node (ref "R13") (pin "2") (pinfunction "2_2") (pintype "passive"))
    )
    (net (code "38") (name "MISO1") (class "Default")
      (node (ref "IC1") (pin "61") (pinfunction "P0[17]/CTS1/MISO0/MISO_61") (pintype "bidirectional"))
      (node (ref "JP3") (pin "1") (pinfunction "1_1") (pintype "passive"))
    )
    (net (code "39") (name "MOSFET_DRIVE") (class "Default")
      (node (ref "C60") (pin "+") (pinfunction "+_+") (pintype "passive"))
      (node (ref "IC9") (pin "3") (pinfunction "VI_3") (pintype "input"))
      (node (ref "J5") (pin "P$4") (pinfunction "GND_P$4") (pintype "bidirectional"))
      (node (ref "J7") (pin "1") (pinfunction "1_1") (pintype "passive"))
      (node (ref "J9") (pin "2") (pinfunction "2_2") (pintype "passive"))
      (node (ref "JP11") (pin "1") (pinfunction "1_1") (pintype "passive"))
      (node (ref "JP27") (pin "1") (pinfunction "1_1") (pintype "passive"))
      (node (ref "R67") (pin "1") (pinfunction "1_1") (pintype "passive"))
      (node (ref "R68") (pin "1") (pinfunction "1_1") (pintype "passive"))
      (node (ref "X10") (pin "2") (pinfunction "2_2") (pintype "passive"))
      (node (ref "X5") (pin "1") (pinfunction "1_1") (pintype "passive"))
      (node (ref "X9") (pin "1") (pinfunction "1_1") (pintype "passive"))
    )
    (net (code "40") (name "MOSI1") (class "Default")
      (node (ref "IC1") (pin "60") (pinfunction "P0[18]/DCD1/MOSI0/MOSI_60") (pintype "bidirectional"))
      (node (ref "JP3") (pin "2") (pinfunction "2_2") (pintype "passive"))
    )
    (net (code "41") (name "MS1") (class "Default")
      (node (ref "IC2") (pin "P05") (pinfunction "MS1_P05") (pintype "bidirectional"))
      (node (ref "IC3") (pin "P05") (pinfunction "MS1_P05") (pintype "bidirectional"))
      (node (ref "IC5") (pin "P05") (pinfunction "MS1_P05") (pintype "bidirectional"))
      (node (ref "IC6") (pin "P05") (pinfunction "MS1_P05") (pintype "bidirectional"))
      (node (ref "JP31") (pin "2") (pinfunction "2_2") (pintype "passive"))
    )
    (net (code "42") (name "MS2") (class "Default")
      (node (ref "IC2") (pin "P06") (pinfunction "MS2_P06") (pintype "bidirectional"))
      (node (ref "IC3") (pin "P06") (pinfunction "MS2_P06") (pintype "bidirectional"))
      (node (ref "IC5") (pin "P06") (pinfunction "MS2_P06") (pintype "bidirectional"))
      (node (ref "IC6") (pin "P06") (pinfunction "MS2_P06") (pintype "bidirectional"))
      (node (ref "JP30") (pin "1") (pinfunction "1_1") (pintype "passive"))
    )
    (net (code "43") (name "Net-(C45-+)") (class "Default")
      (node (ref "C45") (pin "A") (pinfunction "+_A") (pintype "passive"))
      (node (ref "C46") (pin "1") (pinfunction "1_1") (pintype "passive"))
      (node (ref "C47") (pin "1") (pinfunction "1_1") (pintype "passive"))
      (node (ref "C52") (pin "1") (pinfunction "1_1") (pintype "passive"))
      (node (ref "C53") (pin "1") (pinfunction "1_1") (pintype "passive"))
      (node (ref "FB1") (pin "2") (pinfunction "P$2_2") (pintype "bidirectional"))
      (node (ref "IC8") (pin "1") (pinfunction "VDD2A_1") (pintype "bidirectional"))
      (node (ref "IC8") (pin "19") (pinfunction "VDD1A_19") (pintype "bidirectional"))
      (node (ref "R54") (pin "1") (pinfunction "1_1") (pintype "passive"))
      (node (ref "R55") (pin "1") (pinfunction "1_1") (pintype "passive"))
      (node (ref "R56") (pin "1") (pinfunction "1_1") (pintype "passive"))
      (node (ref "R57") (pin "1") (pinfunction "1_1") (pintype "passive"))
      (node (ref "RJ1") (pin "P4") (pinfunction "P4_P4") (pintype "bidirectional"))
      (node (ref "RJ1") (pin "P5") (pinfunction "P5_P5") (pintype "bidirectional"))
    )
    (net (code "44") (name "Net-(C48-+)") (class "Default")
      (node (ref "C48") (pin "A") (pinfunction "+_A") (pintype "passive"))
      (node (ref "C49") (pin "1") (pinfunction "1_1") (pintype "passive"))
      (node (ref "IC8") (pin "6") (pinfunction "VDDCR_6") (pintype "bidirectional"))
    )
    (net (code "45") (name "Net-(C61-+)") (class "Default")
      (node (ref "C61") (pin "A") (pinfunction "+_A") (pintype "passive"))
      (node (ref "J6") (pin "1") (pinfunction "1_1") (pintype "passive"))
      (node (ref "J8") (pin "2") (pinfunction "2_2") (pintype "passive"))
      (node (ref "JP28") (pin "1") (pinfunction "1_1") (pintype "passive"))
      (node (ref "R65") (pin "1") (pinfunction "1_1") (pintype "passive"))
      (node (ref "R66") (pin "1") (pinfunction "1_1") (pintype "passive"))
      (node (ref "X6") (pin "1") (pinfunction "1_1") (pintype "passive"))
      (node (ref "X7") (pin "1") (pinfunction "1_1") (pintype "passive"))
      (node (ref "X8") (pin "1") (pinfunction "1_1") (pintype "passive"))
    )
    (net (code "46") (name "Net-(CN1-PadD+)") (class "Default")
      (node (ref "CN1") (pin "D+") (pinfunction "D+_D+") (pintype "bidirectional"))
      (node (ref "R8") (pin "1") (pinfunction "1_1") (pintype "passive"))
    )
    (net (code "47") (name "Net-(CN1-PadD-)") (class "Default")
      (node (ref "CN1") (pin "D-") (pinfunction "D-_D-") (pintype "bidirectional"))
      (node (ref "R9") (pin "1") (pinfunction "1_1") (pintype "passive"))
    )
    (net (code "48") (name "Net-(IC1-VDDA)") (class "Default")
      (node (ref "C6") (pin "1") (pinfunction "1_1") (pintype "passive"))
      (node (ref "IC1") (pin "10") (pinfunction "VDDA_10") (pintype "bidirectional"))
      (node (ref "IC1") (pin "12") (pinfunction "VREFP_12") (pintype "bidirectional"))
      (node (ref "L1") (pin "1") (pinfunction "1_1") (pintype "passive"))
    )
    (net (code "49") (name "Net-(IC1-XTAL1)") (class "Default")
      (node (ref "C2") (pin "1") (pinfunction "1_1") (pintype "passive"))
      (node (ref "IC1") (pin "22") (pinfunction "XTAL1_22") (pintype "bidirectional"))
      (node (ref "Q2") (pin "2") (pinfunction "2_2") (pintype "passive"))
    )
    (net (code "50") (name "Net-(IC1-XTAL2)") (class "Default")
      (node (ref "C3") (pin "1") (pinfunction "1_1") (pintype "passive"))
      (node (ref "IC1") (pin "23") (pinfunction "XTAL2_23") (pintype "bidirectional"))
      (node (ref "Q2") (pin "1") (pinfunction "1_1") (pintype "passive"))
    )
    (net (code "51") (name "Net-(IC2-CP1)") (class "Default")
      (node (ref "C19") (pin "2") (pinfunction "2_2") (pintype "passive"))
      (node (ref "IC2") (pin "P01") (pinfunction "CP1_P01") (pintype "bidirectional"))
    )
    (net (code "52") (name "Net-(IC2-CP2)") (class "Default")
      (node (ref "C19") (pin "1") (pinfunction "1_1") (pintype "passive"))
      (node (ref "IC2") (pin "P02") (pinfunction "CP2_P02") (pintype "bidirectional"))
    )
    (net (code "53") (name "Net-(IC2-OUT1A)") (class "Default")
      (node (ref "IC2") (pin "P18") (pinfunction "OUT1A_P18") (pintype "bidirectional"))
      (node (ref "J1") (pin "2") (pinfunction "2_2") (pintype "passive"))
      (node (ref "X1") (pin "2") (pinfunction "2_2") (pintype "passive"))
    )
    (net (code "54") (name "Net-(IC2-OUT1B)") (class "Default")
      (node (ref "IC2") (pin "P15") (pinfunction "OUT1B_P15") (pintype "bidirectional"))
      (node (ref "J1") (pin "1") (pinfunction "1_1") (pintype "passive"))
      (node (ref "X1") (pin "1") (pinfunction "1_1") (pintype "passive"))
    )
    (net (code "55") (name "Net-(IC2-OUT2A)") (class "Default")
      (node (ref "IC2") (pin "P19") (pinfunction "OUT2A_P19") (pintype "bidirectional"))
      (node (ref "J1") (pin "3") (pinfunction "3_3") (pintype "passive"))
      (node (ref "X1") (pin "3") (pinfunction "3_3") (pintype "passive"))
    )
    (net (code "56") (name "Net-(IC2-OUT2B)") (class "Default")
      (node (ref "IC2") (pin "P22") (pinfunction "OUT2B_P22") (pintype "bidirectional"))
      (node (ref "J1") (pin "4") (pinfunction "4_4") (pintype "passive"))
      (node (ref "X1") (pin "4") (pinfunction "4_4") (pintype "passive"))
    )
    (net (code "57") (name "Net-(IC2-ROSC)") (class "Default")
      (node (ref "IC2") (pin "P08") (pinfunction "ROSC_P08") (pintype "bidirectional"))
      (node (ref "R22") (pin "2") (pinfunction "2_2") (pintype "passive"))
      (node (ref "R26") (pin "1") (pinfunction "1_1") (pintype "passive"))
    )
    (net (code "58") (name "Net-(IC2-SENSE1)") (class "Default")
      (node (ref "IC2") (pin "P17") (pinfunction "SENSE1_P17") (pintype "bidirectional"))
      (node (ref "R31") (pin "2") (pinfunction "2_2") (pintype "passive"))
    )
    (net (code "59") (name "Net-(IC2-SENSE2)") (class "Default")
      (node (ref "IC2") (pin "P20") (pinfunction "SENSE2_P20") (pintype "bidirectional"))
      (node (ref "R32") (pin "2") (pinfunction "2_2") (pintype "passive"))
    )
    (net (code "60") (name "Net-(IC2-VCP)") (class "Default")
      (node (ref "C17") (pin "2") (pinfunction "2_2") (pintype "passive"))
      (node (ref "IC2") (pin "P03") (pinfunction "VCP_P03") (pintype "bidirectional"))
    )
    (net (code "61") (name "Net-(IC2-VREG)") (class "Default")
      (node (ref "C15") (pin "2") (pinfunction "2_2") (pintype "passive"))
      (node (ref "IC2") (pin "P04") (pinfunction "VREG_P04") (pintype "bidirectional"))
    )
    (net (code "62") (name "Net-(IC2-^RESET)") (class "Default")
      (node (ref "IC2") (pin "P07") (pinfunction "^RESET_P07") (pintype "bidirectional"))
      (node (ref "R25") (pin "1") (pinfunction "1_1") (pintype "passive"))
    )
    (net (code "63") (name "Net-(IC2-^SLEEP)") (class "Default")
      (node (ref "IC2") (pin "P09") (pinfunction "^SLEEP_P09") (pintype "bidirectional"))
      (node (ref "R24") (pin "1") (pinfunction "1_1") (pintype "passive"))
    )
    (net (code "64") (name "Net-(IC3-CP1)") (class "Default")
      (node (ref "C20") (pin "2") (pinfunction "2_2") (pintype "passive"))
      (node (ref "IC3") (pin "P01") (pinfunction "CP1_P01") (pintype "bidirectional"))
    )
    (net (code "65") (name "Net-(IC3-CP2)") (class "Default")
      (node (ref "C20") (pin "1") (pinfunction "1_1") (pintype "passive"))
      (node (ref "IC3") (pin "P02") (pinfunction "CP2_P02") (pintype "bidirectional"))
    )
    (net (code "66") (name "Net-(IC3-OUT1A)") (class "Default")
      (node (ref "IC3") (pin "P18") (pinfunction "OUT1A_P18") (pintype "bidirectional"))
      (node (ref "J2") (pin "2") (pinfunction "2_2") (pintype "passive"))
      (node (ref "X2") (pin "2") (pinfunction "2_2") (pintype "passive"))
    )
    (net (code "67") (name "Net-(IC3-OUT1B)") (class "Default")
      (node (ref "IC3") (pin "P15") (pinfunction "OUT1B_P15") (pintype "bidirectional"))
      (node (ref "J2") (pin "1") (pinfunction "1_1") (pintype "passive"))
      (node (ref "X2") (pin "1") (pinfunction "1_1") (pintype "passive"))
    )
    (net (code "68") (name "Net-(IC3-OUT2A)") (class "Default")
      (node (ref "IC3") (pin "P19") (pinfunction "OUT2A_P19") (pintype "bidirectional"))
      (node (ref "J2") (pin "3") (pinfunction "3_3") (pintype "passive"))
      (node (ref "X2") (pin "3") (pinfunction "3_3") (pintype "passive"))
    )
    (net (code "69") (name "Net-(IC3-OUT2B)") (class "Default")
      (node (ref "IC3") (pin "P22") (pinfunction "OUT2B_P22") (pintype "bidirectional"))
      (node (ref "J2") (pin "4") (pinfunction "4_4") (pintype "passive"))
      (node (ref "X2") (pin "4") (pinfunction "4_4") (pintype "passive"))
    )
    (net (code "70") (name "Net-(IC3-ROSC)") (class "Default")
      (node (ref "IC3") (pin "P08") (pinfunction "ROSC_P08") (pintype "bidirectional"))
      (node (ref "R23") (pin "1") (pinfunction "1_1") (pintype "passive"))
      (node (ref "R27") (pin "1") (pinfunction "1_1") (pintype "passive"))
    )
    (net (code "71") (name "Net-(IC3-SENSE1)") (class "Default")
      (node (ref "IC3") (pin "P17") (pinfunction "SENSE1_P17") (pintype "bidirectional"))
      (node (ref "R33") (pin "2") (pinfunction "2_2") (pintype "passive"))
    )
    (net (code "72") (name "Net-(IC3-SENSE2)") (class "Default")
      (node (ref "IC3") (pin "P20") (pinfunction "SENSE2_P20") (pintype "bidirectional"))
      (node (ref "R34") (pin "2") (pinfunction "2_2") (pintype "passive"))
    )
    (net (code "73") (name "Net-(IC3-VCP)") (class "Default")
      (node (ref "C18") (pin "2") (pinfunction "2_2") (pintype "passive"))
      (node (ref "IC3") (pin "P03") (pinfunction "VCP_P03") (pintype "bidirectional"))
    )
    (net (code "74") (name "Net-(IC3-VREG)") (class "Default")
      (node (ref "C16") (pin "2") (pinfunction "2_2") (pintype "passive"))
      (node (ref "IC3") (pin "P04") (pinfunction "VREG_P04") (pintype "bidirectional"))
    )
    (net (code "75") (name "Net-(IC3-^RESET)") (class "Default")
      (node (ref "IC3") (pin "P07") (pinfunction "^RESET_P07") (pintype "bidirectional"))
      (node (ref "R29") (pin "1") (pinfunction "1_1") (pintype "passive"))
    )
    (net (code "76") (name "Net-(IC3-^SLEEP)") (class "Default")
      (node (ref "IC3") (pin "P09") (pinfunction "^SLEEP_P09") (pintype "bidirectional"))
      (node (ref "R28") (pin "1") (pinfunction "1_1") (pintype "passive"))
    )
    (net (code "77") (name "Net-(IC4-P0A)") (class "Default")
      (node (ref "IC4") (pin "1") (pinfunction "P3A_1") (pintype "bidirectional"))
      (node (ref "IC4") (pin "10") (pinfunction "P1A_10") (pintype "bidirectional"))
      (node (ref "IC4") (pin "11") (pinfunction "P0A_11") (pintype "bidirectional"))
      (node (ref "IC4") (pin "20") (pinfunction "P2A_20") (pintype "bidirectional"))
      (node (ref "R30") (pin "1") (pinfunction "1_1") (pintype "passive"))
    )
    (net (code "78") (name "Net-(IC4-~{RESET})") (class "Default")
      (node (ref "IC4") (pin "15") (pinfunction "~{RESET}_15") (pintype "bidirectional"))
      (node (ref "R37") (pin "1") (pinfunction "1_1") (pintype "passive"))
    )
    (net (code "79") (name "Net-(IC5-CP1)") (class "Default")
      (node (ref "C36") (pin "2") (pinfunction "2_2") (pintype "passive"))
      (node (ref "IC5") (pin "P01") (pinfunction "CP1_P01") (pintype "bidirectional"))
    )
    (net (code "80") (name "Net-(IC5-CP2)") (class "Default")
      (node (ref "C36") (pin "1") (pinfunction "1_1") (pintype "passive"))
      (node (ref "IC5") (pin "P02") (pinfunction "CP2_P02") (pintype "bidirectional"))
    )
    (net (code "81") (name "Net-(IC5-OUT1A)") (class "Default")
      (node (ref "IC5") (pin "P18") (pinfunction "OUT1A_P18") (pintype "bidirectional"))
      (node (ref "J3") (pin "2") (pinfunction "2_2") (pintype "passive"))
      (node (ref "X3") (pin "2") (pinfunction "2_2") (pintype "passive"))
    )
    (net (code "82") (name "Net-(IC5-OUT1B)") (class "Default")
      (node (ref "IC5") (pin "P15") (pinfunction "OUT1B_P15") (pintype "bidirectional"))
      (node (ref "J3") (pin "1") (pinfunction "1_1") (pintype "passive"))
      (node (ref "X3") (pin "1") (pinfunction "1_1") (pintype "passive"))
    )
    (net (code "83") (name "Net-(IC5-OUT2A)") (class "Default")
      (node (ref "IC5") (pin "P19") (pinfunction "OUT2A_P19") (pintype "bidirectional"))
      (node (ref "J3") (pin "3") (pinfunction "3_3") (pintype "passive"))
      (node (ref "X3") (pin "3") (pinfunction "3_3") (pintype "passive"))
    )
    (net (code "84") (name "Net-(IC5-OUT2B)") (class "Default")
      (node (ref "IC5") (pin "P22") (pinfunction "OUT2B_P22") (pintype "bidirectional"))
      (node (ref "J3") (pin "4") (pinfunction "4_4") (pintype "passive"))
      (node (ref "X3") (pin "4") (pinfunction "4_4") (pintype "passive"))
    )
    (net (code "85") (name "Net-(IC5-ROSC)") (class "Default")
      (node (ref "IC5") (pin "P08") (pinfunction "ROSC_P08") (pintype "bidirectional"))
      (node (ref "R38") (pin "1") (pinfunction "1_1") (pintype "passive"))
      (node (ref "R40") (pin "1") (pinfunction "1_1") (pintype "passive"))
    )
    (net (code "86") (name "Net-(IC5-SENSE1)") (class "Default")
      (node (ref "IC5") (pin "P17") (pinfunction "SENSE1_P17") (pintype "bidirectional"))
      (node (ref "R46") (pin "2") (pinfunction "2_2") (pintype "passive"))
    )
    (net (code "87") (name "Net-(IC5-SENSE2)") (class "Default")
      (node (ref "IC5") (pin "P20") (pinfunction "SENSE2_P20") (pintype "bidirectional"))
      (node (ref "R47") (pin "2") (pinfunction "2_2") (pintype "passive"))
    )
    (net (code "88") (name "Net-(IC5-VCP)") (class "Default")
      (node (ref "C34") (pin "2") (pinfunction "2_2") (pintype "passive"))
      (node (ref "IC5") (pin "P03") (pinfunction "VCP_P03") (pintype "bidirectional"))
    )
    (net (code "89") (name "Net-(IC5-VREG)") (class "Default")
      (node (ref "C32") (pin "2") (pinfunction "2_2") (pintype "passive"))
      (node (ref "IC5") (pin "P04") (pinfunction "VREG_P04") (pintype "bidirectional"))
    )
    (net (code "90") (name "Net-(IC5-^RESET)") (class "Default")
      (node (ref "IC5") (pin "P07") (pinfunction "^RESET_P07") (pintype "bidirectional"))
      (node (ref "R42") (pin "1") (pinfunction "1_1") (pintype "passive"))
    )
    (net (code "91") (name "Net-(IC5-^SLEEP)") (class "Default")
      (node (ref "IC5") (pin "P09") (pinfunction "^SLEEP_P09") (pintype "bidirectional"))
      (node (ref "R41") (pin "1") (pinfunction "1_1") (pintype "passive"))
    )
    (net (code "92") (name "Net-(IC6-CP1)") (class "Default")
      (node (ref "C37") (pin "2") (pinfunction "2_2") (pintype "passive"))
      (node (ref "IC6") (pin "P01") (pinfunction "CP1_P01") (pintype "bidirectional"))
    )
    (net (code "93") (name "Net-(IC6-CP2)") (class "Default")
      (node (ref "C37") (pin "1") (pinfunction "1_1") (pintype "passive"))
      (node (ref "IC6") (pin "P02") (pinfunction "CP2_P02") (pintype "bidirectional"))
    )
    (net (code "94") (name "Net-(IC6-OUT1A)") (class "Default")
      (node (ref "IC6") (pin "P18") (pinfunction "OUT1A_P18") (pintype "bidirectional"))
      (node (ref "J4") (pin "2") (pinfunction "2_2") (pintype "passive"))
      (node (ref "X4") (pin "2") (pinfunction "2_2") (pintype "passive"))
    )
    (net (code "95") (name "Net-(IC6-OUT1B)") (class "Default")
      (node (ref "IC6") (pin "P15") (pinfunction "OUT1B_P15") (pintype "bidirectional"))
      (node (ref "J4") (pin "1") (pinfunction "1_1") (pintype "passive"))
      (node (ref "X4") (pin "1") (pinfunction "1_1") (pintype "passive"))
    )
    (net (code "96") (name "Net-(IC6-OUT2A)") (class "Default")
      (node (ref "IC6") (pin "P19") (pinfunction "OUT2A_P19") (pintype "bidirectional"))
      (node (ref "J4") (pin "3") (pinfunction "3_3") (pintype "passive"))
      (node (ref "X4") (pin "3") (pinfunction "3_3") (pintype "passive"))
    )
    (net (code "97") (name "Net-(IC6-OUT2B)") (class "Default")
      (node (ref "IC6") (pin "P22") (pinfunction "OUT2B_P22") (pintype "bidirectional"))
      (node (ref "J4") (pin "4") (pinfunction "4_4") (pintype "passive"))
      (node (ref "X4") (pin "4") (pinfunction "4_4") (pintype "passive"))
    )
    (net (code "98") (name "Net-(IC6-ROSC)") (class "Default")
      (node (ref "IC6") (pin "P08") (pinfunction "ROSC_P08") (pintype "bidirectional"))
      (node (ref "R39") (pin "1") (pinfunction "1_1") (pintype "passive"))
      (node (ref "R43") (pin "1") (pinfunction "1_1") (pintype "passive"))
    )
    (net (code "99") (name "Net-(IC6-SENSE1)") (class "Default")
      (node (ref "IC6") (pin "P17") (pinfunction "SENSE1_P17") (pintype "bidirectional"))
      (node (ref "R48") (pin "2") (pinfunction "2_2") (pintype "passive"))
    )
    (net (code "100") (name "Net-(IC6-SENSE2)") (class "Default")
      (node (ref "IC6") (pin "P20") (pinfunction "SENSE2_P20") (pintype "bidirectional"))
      (node (ref "R49") (pin "2") (pinfunction "2_2") (pintype "passive"))
    )
    (net (code "101") (name "Net-(IC6-VCP)") (class "Default")
      (node (ref "C35") (pin "2") (pinfunction "2_2") (pintype "passive"))
      (node (ref "IC6") (pin "P03") (pinfunction "VCP_P03") (pintype "bidirectional"))
    )
    (net (code "102") (name "Net-(IC6-VREG)") (class "Default")
      (node (ref "C33") (pin "2") (pinfunction "2_2") (pintype "passive"))
      (node (ref "IC6") (pin "P04") (pinfunction "VREG_P04") (pintype "bidirectional"))
    )
    (net (code "103") (name "Net-(IC6-^RESET)") (class "Default")
      (node (ref "IC6") (pin "P07") (pinfunction "^RESET_P07") (pintype "bidirectional"))
      (node (ref "R45") (pin "1") (pinfunction "1_1") (pintype "passive"))
    )
    (net (code "104") (name "Net-(IC6-^SLEEP)") (class "Default")
      (node (ref "IC6") (pin "P09") (pinfunction "^SLEEP_P09") (pintype "bidirectional"))
      (node (ref "R44") (pin "1") (pinfunction "1_1") (pintype "passive"))
    )
    (net (code "105") (name "Net-(IC7-A)") (class "Default")
      (node (ref "IC7") (pin "2") (pinfunction "A_2") (pintype "bidirectional"))
      (node (ref "IC8") (pin "14") (pinfunction "NINT/REFCLKO_14") (pintype "bidirectional"))
    )
    (net (code "106") (name "Net-(IC7-Y)") (class "Default")
      (node (ref "IC7") (pin "4") (pinfunction "Y_4") (pintype "bidirectional"))
      (node (ref "R51") (pin "1") (pinfunction "1_1") (pintype "passive"))
    )
    (net (code "107") (name "Net-(IC8-CRS_DV)") (class "Default")
      (node (ref "IC8") (pin "11") (pinfunction "CRS_DV_11") (pintype "bidirectional"))
      (node (ref "R60") (pin "1") (pinfunction "1_1") (pintype "passive"))
    )
    (net (code "108") (name "Net-(IC8-RBIAS)") (class "Default")
      (node (ref "IC8") (pin "24") (pinfunction "RBIAS_24") (pintype "bidirectional"))
      (node (ref "R63") (pin "2") (pinfunction "2_2") (pintype "passive"))
    )
    (net (code "109") (name "Net-(IC8-RXD0)") (class "Default")
      (node (ref "IC8") (pin "8") (pinfunction "RXD0_8") (pintype "bidirectional"))
      (node (ref "R58") (pin "1") (pinfunction "1_1") (pintype "passive"))
    )
    (net (code "110") (name "Net-(IC8-RXD1)") (class "Default")
      (node (ref "IC8") (pin "7") (pinfunction "RXD1_7") (pintype "bidirectional"))
      (node (ref "R59") (pin "1") (pinfunction "1_1") (pintype "passive"))
    )
    (net (code "111") (name "Net-(IC8-XTAL1)") (class "Default")
      (node (ref "C58") (pin "1") (pinfunction "1_1") (pintype "passive"))
      (node (ref "IC8") (pin "5") (pinfunction "XTAL1_5") (pintype "bidirectional"))
      (node (ref "Q3") (pin "2") (pinfunction "2_2") (pintype "passive"))
      (node (ref "R64") (pin "1") (pinfunction "1_1") (pintype "passive"))
    )
    (net (code "112") (name "Net-(IC8-XTAL2)") (class "Default")
      (node (ref "C59") (pin "1") (pinfunction "1_1") (pintype "passive"))
      (node (ref "IC8") (pin "4") (pinfunction "XTAL2_4") (pintype "bidirectional"))
      (node (ref "Q3") (pin "1") (pinfunction "1_1") (pintype "passive"))
      (node (ref "R64") (pin "2") (pinfunction "2_2") (pintype "passive"))
    )
    (net (code "113") (name "Net-(IC9-VO)") (class "Default")
      (node (ref "C62") (pin "1") (pinfunction "1_1") (pintype "passive"))
      (node (ref "C66") (pin "1") (pinfunction "1_1") (pintype "passive"))
      (node (ref "IC9") (pin "1") (pinfunction "VO_1") (pintype "passive"))
      (node (ref "U$2") (pin "6") (pinfunction "P$1_6") (pintype "bidirectional"))
    )
    (net (code "114") (name "Net-(J7-Pad2)") (class "Default")
      (node (ref "J7") (pin "2") (pinfunction "2_2") (pintype "passive"))
      (node (ref "LED8") (pin "C") (pinfunction "C_C") (pintype "passive"))
      (node (ref "Q7") (pin "D") (pinfunction "D_D") (pintype "passive"))
      (node (ref "X9") (pin "2") (pinfunction "2_2") (pintype "passive"))
    )
    (net (code "115") (name "Net-(J9-Pad1)") (class "Default")
      (node (ref "J9") (pin "1") (pinfunction "1_1") (pintype "passive"))
      (node (ref "LED7") (pin "C") (pinfunction "C_C") (pintype "passive"))
      (node (ref "Q6") (pin "D") (pinfunction "D_D") (pintype "passive"))
      (node (ref "X10") (pin "1") (pinfunction "1_1") (pintype "passive"))
    )
    (net (code "116") (name "Net-(JP24-Pad1)") (class "Default")
      (node (ref "JP24") (pin "1") (pinfunction "1_1") (pintype "passive"))
      (node (ref "R17") (pin "2") (pinfunction "2_2") (pintype "passive"))
      (node (ref "S3") (pin "C") (pinfunction "C_C") (pintype "passive"))
    )
    (net (code "117") (name "Net-(LED1-PadA)") (class "Default")
      (node (ref "LED1") (pin "A") (pinfunction "A_A") (pintype "passive"))
      (node (ref "R10") (pin "1") (pinfunction "1_1") (pintype "passive"))
    )
    (net (code "118") (name "Net-(LED2-PadA)") (class "Default")
      (node (ref "LED2") (pin "A") (pinfunction "A_A") (pintype "passive"))
      (node (ref "R11") (pin "1") (pinfunction "1_1") (pintype "passive"))
    )
    (net (code "119") (name "Net-(LED3-PadA)") (class "Default")
      (node (ref "LED3") (pin "A") (pinfunction "A_A") (pintype "passive"))
      (node (ref "R12") (pin "1") (pinfunction "1_1") (pintype "passive"))
    )
    (net (code "120") (name "Net-(LED4-PadA)") (class "Default")
      (node (ref "LED4") (pin "A") (pinfunction "A_A") (pintype "passive"))
      (node (ref "R13") (pin "1") (pinfunction "1_1") (pintype "passive"))
    )
    (net (code "121") (name "Net-(LED5-PadA)") (class "Default")
      (node (ref "LED5") (pin "A") (pinfunction "A_A") (pintype "passive"))
      (node (ref "R65") (pin "2") (pinfunction "2_2") (pintype "passive"))
    )
    (net (code "122") (name "Net-(LED6-PadA)") (class "Default")
      (node (ref "LED6") (pin "A") (pinfunction "A_A") (pintype "passive"))
      (node (ref "R66") (pin "2") (pinfunction "2_2") (pintype "passive"))
    )
    (net (code "123") (name "Net-(LED7-PadA)") (class "Default")
      (node (ref "LED7") (pin "A") (pinfunction "A_A") (pintype "passive"))
      (node (ref "R67") (pin "2") (pinfunction "2_2") (pintype "passive"))
    )
    (net (code "124") (name "Net-(LED8-PadA)") (class "Default")
      (node (ref "LED8") (pin "A") (pinfunction "A_A") (pintype "passive"))
      (node (ref "R68") (pin "2") (pinfunction "2_2") (pintype "passive"))
    )
    (net (code "125") (name "Net-(LED9-PadA)") (class "Default")
      (node (ref "LED9") (pin "A") (pinfunction "A_A") (pintype "passive"))
      (node (ref "R77") (pin "1") (pinfunction "1_1") (pintype "passive"))
    )
    (net (code "126") (name "Net-(LED10-PadA)") (class "Default")
      (node (ref "LED10") (pin "A") (pinfunction "A_A") (pintype "passive"))
      (node (ref "R78") (pin "1") (pinfunction "1_1") (pintype "passive"))
    )
    (net (code "127") (name "Net-(Q1-PadB)") (class "Default")
      (node (ref "Q1") (pin "B") (pinfunction "B_B") (pintype "passive"))
      (node (ref "R4") (pin "1") (pinfunction "1_1") (pintype "passive"))
    )
    (net (code "128") (name "Net-(Q1-PadC)") (class "Default")
      (node (ref "Q1") (pin "C") (pinfunction "C_C") (pintype "passive"))
      (node (ref "R7") (pin "2") (pinfunction "2_2") (pintype "passive"))
    )
    (net (code "129") (name "Net-(Q8-D)") (class "Default")
      (node (ref "J8") (pin "1") (pinfunction "1_1") (pintype "passive"))
      (node (ref "LED5") (pin "C") (pinfunction "C_C") (pintype "passive"))
      (node (ref "Q8") (pin "4") (pinfunction "D_4") (pintype "passive"))
      (node (ref "X7") (pin "2") (pinfunction "2_2") (pintype "passive"))
    )
    (net (code "130") (name "Net-(Q8-G)") (class "Default")
      (node (ref "Q8") (pin "1") (pinfunction "G_1") (pintype "passive"))
      (node (ref "R73") (pin "1") (pinfunction "1_1") (pintype "passive"))
    )
    (net (code "131") (name "Net-(Q9-D)") (class "Default")
      (node (ref "J6") (pin "2") (pinfunction "2_2") (pintype "passive"))
      (node (ref "LED6") (pin "C") (pinfunction "C_C") (pintype "passive"))
      (node (ref "Q9") (pin "4") (pinfunction "D_4") (pintype "passive"))
      (node (ref "X8") (pin "2") (pinfunction "2_2") (pintype "passive"))
    )
    (net (code "132") (name "Net-(Q9-G)") (class "Default")
      (node (ref "Q9") (pin "1") (pinfunction "G_1") (pintype "passive"))
      (node (ref "R75") (pin "1") (pinfunction "1_1") (pintype "passive"))
    )
    (net (code "133") (name "Net-(R50-Pad2)") (class "Default")
      (node (ref "R50") (pin "2") (pinfunction "2_2") (pintype "passive"))
      (node (ref "RJ1") (pin "Y-") (pinfunction "Y-_Y-") (pintype "bidirectional"))
    )
    (net (code "134") (name "Net-(R61-Pad2)") (class "Default")
      (node (ref "R61") (pin "2") (pinfunction "2_2") (pintype "passive"))
      (node (ref "RJ1") (pin "G-") (pinfunction "G-_G-") (pintype "bidirectional"))
    )
    (net (code "135") (name "Net-(U$2A-P$2)") (class "Default")
      (node (ref "R69") (pin "1") (pinfunction "1_1") (pintype "passive"))
      (node (ref "U$2") (pin "7") (pinfunction "P$2_7") (pintype "bidirectional"))
    )
    (net (code "136") (name "Net-(U$2B-P$2)") (class "Default")
      (node (ref "R70") (pin "1") (pinfunction "1_1") (pintype "passive"))
      (node (ref "U$2") (pin "5") (pinfunction "P$2_5") (pintype "bidirectional"))
    )
    (net (code "137") (name "P0W") (class "Default")
      (node (ref "IC2") (pin "P12") (pinfunction "REF_P12") (pintype "bidirectional"))
      (node (ref "IC4") (pin "12") (pinfunction "P0W_12") (pintype "bidirectional"))
    )
    (net (code "138") (name "P1W") (class "Default")
      (node (ref "IC3") (pin "P12") (pinfunction "REF_P12") (pintype "bidirectional"))
      (node (ref "IC4") (pin "9") (pinfunction "P1W_9") (pintype "bidirectional"))
    )
    (net (code "139") (name "P1_22") (class "Default")
      (node (ref "IC1") (pin "36") (pinfunction "P1[22]/MC0B/USB_PWRD/MAT1[0]_36") (pintype "bidirectional"))
      (node (ref "JP8") (pin "1") (pinfunction "1_1") (pintype "passive"))
    )
    (net (code "140") (name "P1_23") (class "Default")
      (node (ref "IC1") (pin "37") (pinfunction "P1[23]/MCFB1/PWM1[4]/MISO0_37") (pintype "bidirectional"))
      (node (ref "JP8") (pin "2") (pinfunction "2_2") (pintype "passive"))
    )
    (net (code "141") (name "P1_30") (class "Default")
      (node (ref "IC1") (pin "21") (pinfunction "P1[30]/VBUS/AD0[4]_21") (pintype "bidirectional"))
      (node (ref "JP8") (pin "4") (pinfunction "4_4") (pintype "passive"))
    )
    (net (code "142") (name "P1_31") (class "Default")
      (node (ref "IC1") (pin "20") (pinfunction "P1[31]/SCK1/AD0[5]_20") (pintype "bidirectional"))
      (node (ref "JP8") (pin "3") (pinfunction "3_3") (pintype "passive"))
    )
    (net (code "143") (name "P2.6") (class "Default")
      (node (ref "IC1") (pin "67") (pinfunction "P2[6]/PCAP1[0]/RI1/TRACECLK_67") (pintype "bidirectional"))
      (node (ref "JP13") (pin "1") (pinfunction "1_1") (pintype "passive"))
      (node (ref "R75") (pin "2") (pinfunction "2_2") (pintype "passive"))
      (node (ref "R76") (pin "1") (pinfunction "1_1") (pintype "passive"))
    )
    (net (code "144") (name "P2.7") (class "Default")
      (node (ref "IC1") (pin "66") (pinfunction "P2[7]/RD2/RTS1_66") (pintype "bidirectional"))
      (node (ref "JP13") (pin "4") (pinfunction "4_4") (pintype "passive"))
      (node (ref "R72") (pin "2") (pinfunction "2_2") (pintype "passive"))
      (node (ref "U$2") (pin "4") (pinfunction "P$1_4") (pintype "bidirectional"))
    )
    (net (code "145") (name "P2.8") (class "Default")
      (node (ref "IC1") (pin "65") (pinfunction "P2[8]/TD2/TXD2_65") (pintype "bidirectional"))
      (node (ref "JP18") (pin "1") (pinfunction "1_1") (pintype "passive"))
    )
    (net (code "146") (name "P2.9") (class "Default")
      (node (ref "IC1") (pin "64") (pinfunction "P2[9]/USB_CONNECT/RXD2_64") (pintype "bidirectional"))
      (node (ref "R4") (pin "2") (pinfunction "2_2") (pintype "passive"))
    )
    (net (code "147") (name "P2.13") (class "Default")
      (node (ref "IC1") (pin "50") (pinfunction "P2[13]/EINT3/I2STX_SDA_50") (pintype "bidirectional"))
      (node (ref "JP18") (pin "3") (pinfunction "3_3") (pintype "passive"))
    )
    (net (code "148") (name "P2W") (class "Default")
      (node (ref "IC4") (pin "19") (pinfunction "P2W_19") (pintype "bidirectional"))
      (node (ref "IC5") (pin "P12") (pinfunction "REF_P12") (pintype "bidirectional"))
    )
    (net (code "149") (name "P3W") (class "Default")
      (node (ref "IC4") (pin "2") (pinfunction "P3W_2") (pintype "bidirectional"))
      (node (ref "IC6") (pin "P12") (pinfunction "REF_P12") (pintype "bidirectional"))
    )
    (net (code "150") (name "P4.29") (class "Default")
      (node (ref "IC1") (pin "85") (pinfunction "P4[29]/TX_MCLK/MAT2[1]/RXD3_85") (pintype "bidirectional"))
      (node (ref "JP18") (pin "2") (pinfunction "2_2") (pintype "passive"))
    )
    (net (code "151") (name "PLAY") (class "Default")
      (node (ref "IC1") (pin "51") (pinfunction "P2[12]/EINT2/I2STX_WS_51") (pintype "bidirectional"))
      (node (ref "JP23") (pin "1") (pinfunction "1_1") (pintype "passive"))
      (node (ref "R16") (pin "1") (pinfunction "1_1") (pintype "passive"))
      (node (ref "S3") (pin "4") (pinfunction "1_4") (pintype "passive"))
    )
    (net (code "152") (name "PLAY_LED") (class "Default")
      (node (ref "IC1") (pin "82") (pinfunction "P4[28]/RX_MCLK/MAT2[0]/TXD3_82") (pintype "bidirectional"))
      (node (ref "JP24") (pin "2") (pinfunction "2_2") (pintype "passive"))
      (node (ref "S3") (pin "A") (pinfunction "A_A") (pintype "passive"))
    )
    (net (code "153") (name "POT_SCL") (class "Default")
      (node (ref "IC1") (pin "47") (pinfunction "P0[1]/TD1/RXD3/SCL1_47") (pintype "bidirectional"))
      (node (ref "IC4") (pin "5") (pinfunction "SCL_5") (pintype "bidirectional"))
      (node (ref "R36") (pin "1") (pinfunction "1_1") (pintype "passive"))
    )
    (net (code "154") (name "POT_SDA") (class "Default")
      (node (ref "IC1") (pin "46") (pinfunction "P0[0]/RD1/TXD3/SDA1_46") (pintype "bidirectional"))
      (node (ref "IC4") (pin "6") (pinfunction "SDA_6") (pintype "bidirectional"))
      (node (ref "R35") (pin "1") (pinfunction "1_1") (pintype "passive"))
    )
    (net (code "155") (name "PWM0") (class "Default")
      (node (ref "IC1") (pin "69") (pinfunction "P2[4]/PWM1[5]/DSR1/TRACEDATA[1]_69") (pintype "bidirectional"))
      (node (ref "JP13") (pin "2") (pinfunction "2_2") (pintype "passive"))
      (node (ref "R73") (pin "2") (pinfunction "2_2") (pintype "passive"))
      (node (ref "R74") (pin "1") (pinfunction "1_1") (pintype "passive"))
    )
    (net (code "156") (name "PWM1") (class "Default")
      (node (ref "IC1") (pin "68") (pinfunction "P2[5]/PWM1[6]/DTR1/TRACEDATA[0]_68") (pintype "bidirectional"))
      (node (ref "JP13") (pin "3") (pinfunction "3_3") (pintype "passive"))
      (node (ref "R71") (pin "2") (pinfunction "2_2") (pintype "passive"))
      (node (ref "U$2") (pin "2") (pinfunction "P$1_2") (pintype "bidirectional"))
    )
    (net (code "157") (name "PWM1_FET") (class "Default")
      (node (ref "Q6") (pin "G") (pinfunction "G_G") (pintype "passive"))
      (node (ref "R69") (pin "2") (pinfunction "2_2") (pintype "passive"))
    )
    (net (code "158") (name "RD+") (class "Default")
      (node (ref "C56") (pin "1") (pinfunction "1_1") (pintype "passive"))
      (node (ref "IC8") (pin "23") (pinfunction "RX+_23") (pintype "bidirectional"))
      (node (ref "R56") (pin "2") (pinfunction "2_2") (pintype "passive"))
      (node (ref "RJ1") (pin "RD+") (pinfunction "RD+_RD+") (pintype "bidirectional"))
    )
    (net (code "159") (name "RD-") (class "Default")
      (node (ref "C57") (pin "1") (pinfunction "1_1") (pintype "passive"))
      (node (ref "IC8") (pin "22") (pinfunction "RX-_22") (pintype "bidirectional"))
      (node (ref "R57") (pin "2") (pinfunction "2_2") (pintype "passive"))
      (node (ref "RJ1") (pin "RD-") (pinfunction "RD-_RD-") (pintype "bidirectional"))
    )
    (net (code "160") (name "RESET") (class "Default")
      (node (ref "IC1") (pin "17") (pinfunction "RESET_17") (pintype "bidirectional"))
      (node (ref "JP25") (pin "1") (pinfunction "1_1") (pintype "passive"))
      (node (ref "R14") (pin "1") (pinfunction "1_1") (pintype "passive"))
      (node (ref "S1") (pin "1") (pinfunction "1_1") (pintype "passive"))
      (node (ref "S1") (pin "2") (pinfunction "2_2") (pintype "passive"))
    )
    (net (code "161") (name "RSTOUT") (class "Default")
      (node (ref "IC1") (pin "14") (pinfunction "RSTOUT_14") (pintype "bidirectional"))
      (node (ref "IC8") (pin "15") (pinfunction "NRST_15") (pintype "bidirectional"))
    )
    (net (code "162") (name "RTS") (class "Default")
      (node (ref "JP5") (pin "6") (pinfunction "6_6") (pintype "passive"))
    )
    (net (code "163") (name "RX_0") (class "Default")
      (node (ref "IC1") (pin "99") (pinfunction "P0[3]/RXD0/AD0[6]_99") (pintype "bidirectional"))
      (node (ref "JP5") (pin "4") (pinfunction "4_4") (pintype "passive"))
    )
    (net (code "164") (name "SCK1") (class "Default")
      (node (ref "IC1") (pin "62") (pinfunction "P0[15]/TXD1/SCK0/SCK_62") (pintype "bidirectional"))
      (node (ref "JP2") (pin "3") (pinfunction "3_3") (pintype "passive"))
    )
    (net (code "165") (name "SCL") (class "Default")
      (node (ref "IC1") (pin "24") (pinfunction "P0[28]/SCL0/USB_SCL_24") (pintype "bidirectional"))
      (node (ref "JP1") (pin "4") (pinfunction "4_4") (pintype "passive"))
      (node (ref "R5") (pin "1") (pinfunction "1_1") (pintype "passive"))
    )
    (net (code "166") (name "SDA") (class "Default")
      (node (ref "IC1") (pin "25") (pinfunction "P0[27]/SDA0/USB_SDA_25") (pintype "bidirectional"))
      (node (ref "JP1") (pin "3") (pinfunction "3_3") (pintype "passive"))
      (node (ref "R6") (pin "1") (pinfunction "1_1") (pintype "passive"))
    )
    (net (code "167") (name "SD_CD") (class "Default")
      (node (ref "IC1") (pin "52") (pinfunction "P2[11]/EINT1/I2STX_CLK_52") (pintype "bidirectional"))
      (node (ref "JP20") (pin "3") (pinfunction "3_3") (pintype "passive"))
    )
    (net (code "168") (name "SD_CS") (class "Default")
      (node (ref "IC1") (pin "79") (pinfunction "P0[6]/I2SRX_SDA/SSEL1/MAT2[0]_79") (pintype "bidirectional"))
      (node (ref "JP4") (pin "2") (pinfunction "2_2") (pintype "passive"))
      (node (ref "R1") (pin "1") (pinfunction "1_1") (pintype "passive"))
      (node (ref "U1") (pin "2") (pinfunction "CS_2") (pintype "bidirectional"))
    )
    (net (code "169") (name "SD_IRQ") (class "Default")
      (node (ref "IC1") (pin "27") (pinfunction "P3[25]/MAT0[0]/PWM1[2]_27") (pintype "bidirectional"))
      (node (ref "JP20") (pin "1") (pinfunction "1_1") (pintype "passive"))
    )
    (net (code "170") (name "SD_MISO") (class "Default")
      (node (ref "IC1") (pin "77") (pinfunction "P0[8]/I2STX_WS/MISO1/MAT2[2]_77") (pintype "bidirectional"))
      (node (ref "JP6") (pin "1") (pinfunction "1_1") (pintype "passive"))
      (node (ref "R2") (pin "1") (pinfunction "1_1") (pintype "passive"))
      (node (ref "U1") (pin "7") (pinfunction "DO_7") (pintype "bidirectional"))
    )
    (net (code "171") (name "SD_MOSI") (class "Default")
      (node (ref "IC1") (pin "76") (pinfunction "P0[9]/I2STX_SDA/MOSI1/MAT2[3]_76") (pintype "bidirectional"))
      (node (ref "JP6") (pin "2") (pinfunction "2_2") (pintype "passive"))
      (node (ref "R3") (pin "1") (pinfunction "1_1") (pintype "passive"))
      (node (ref "U1") (pin "3") (pinfunction "DI_3") (pintype "bidirectional"))
    )
    (net (code "172") (name "SD_SCK") (class "Default")
      (node (ref "IC1") (pin "78") (pinfunction "P0[7]/I2STX_CLK/SCK1/MAT2[1]_78") (pintype "bidirectional"))
      (node (ref "JP4") (pin "3") (pinfunction "3_3") (pintype "passive"))
      (node (ref "U1") (pin "5") (pinfunction "SCK_5") (pintype "bidirectional"))
    )
    (net (code "173") (name "SD_WP") (class "Default")
      (node (ref "IC1") (pin "26") (pinfunction "P3[26]/STCLK/MAT0[1]/PWM1[3]_26") (pintype "bidirectional"))
      (node (ref "JP20") (pin "2") (pinfunction "2_2") (pintype "passive"))
    )
    (net (code "174") (name "SSEL1") (class "Default")
      (node (ref "IC1") (pin "63") (pinfunction "P0[16]/RXD1/SSEL0/SSEL_63") (pintype "bidirectional"))
      (node (ref "JP2") (pin "2") (pinfunction "2_2") (pintype "passive"))
    )
    (net (code "175") (name "STP1") (class "Default")
      (node (ref "IC1") (pin "75") (pinfunction "P2[0]/PWM1[1]/TXD1_75") (pintype "bidirectional"))
      (node (ref "IC2") (pin "P11") (pinfunction "STEP_P11") (pintype "bidirectional"))
      (node (ref "JP7") (pin "3") (pinfunction "3_3") (pintype "passive"))
    )
    (net (code "176") (name "STP2") (class "Default")
      (node (ref "IC1") (pin "74") (pinfunction "P2[1]/PWM1[2]/RXD1_74") (pintype "bidirectional"))
      (node (ref "IC3") (pin "P11") (pinfunction "STEP_P11") (pintype "bidirectional"))
      (node (ref "JP9") (pin "3") (pinfunction "3_3") (pintype "passive"))
    )
    (net (code "177") (name "STP3") (class "Default")
      (node (ref "IC1") (pin "73") (pinfunction "P2[2]/PWM1[3]/CTS1/TRACEDATA[3]_73") (pintype "bidirectional"))
      (node (ref "IC5") (pin "P11") (pinfunction "STEP_P11") (pintype "bidirectional"))
      (node (ref "JP12") (pin "3") (pinfunction "3_3") (pintype "passive"))
    )
    (net (code "178") (name "STP4") (class "Default")
      (node (ref "IC1") (pin "70") (pinfunction "P2[3]/PWM1[4]/DCD1/TRACEDATA[2]_70") (pintype "bidirectional"))
      (node (ref "IC6") (pin "P11") (pinfunction "STEP_P11") (pintype "bidirectional"))
      (node (ref "JP15") (pin "3") (pinfunction "3_3") (pintype "passive"))
    )
    (net (code "179") (name "TD+") (class "Default")
      (node (ref "C54") (pin "1") (pinfunction "1_1") (pintype "passive"))
      (node (ref "IC8") (pin "21") (pinfunction "TX+_21") (pintype "bidirectional"))
      (node (ref "R54") (pin "2") (pinfunction "2_2") (pintype "passive"))
      (node (ref "RJ1") (pin "TD+") (pinfunction "TD+_TD+") (pintype "bidirectional"))
    )
    (net (code "180") (name "TD-") (class "Default")
      (node (ref "C55") (pin "1") (pinfunction "1_1") (pintype "passive"))
      (node (ref "IC8") (pin "20") (pinfunction "TX-_20") (pintype "bidirectional"))
      (node (ref "R55") (pin "2") (pinfunction "2_2") (pintype "passive"))
      (node (ref "RJ1") (pin "TD-") (pinfunction "TD-_TD-") (pintype "bidirectional"))
    )
    (net (code "181") (name "TH1") (class "Default")
      (node (ref "C21") (pin "A") (pinfunction "+_A") (pintype "passive"))
      (node (ref "IC1") (pin "9") (pinfunction "P0[23]/AD0[0]/I2SRX_CLK/CAP3[0]_9") (pintype "bidirectional"))
      (node (ref "RN1") (pin "8") (pinfunction "2_8") (pintype "passive"))
      (node (ref "SL1") (pin "2") (pinfunction "2_2") (pintype "passive"))
    )
    (net (code "182") (name "TH2") (class "Default")
      (node (ref "C22") (pin "A") (pinfunction "+_A") (pintype "passive"))
      (node (ref "IC1") (pin "8") (pinfunction "P0[24]/AD0[1]/I2SRX_WS/CAP3[1]_8") (pintype "bidirectional"))
      (node (ref "RN1") (pin "7") (pinfunction "2_7") (pintype "passive"))
      (node (ref "SL1") (pin "4") (pinfunction "4_4") (pintype "passive"))
    )
    (net (code "183") (name "TH3") (class "Default")
      (node (ref "C23") (pin "A") (pinfunction "+_A") (pintype "passive"))
      (node (ref "IC1") (pin "7") (pinfunction "P0[25]/AD0[2]/I2SRX_SDA/TXD3_7") (pintype "bidirectional"))
      (node (ref "RN1") (pin "6") (pinfunction "2_6") (pintype "passive"))
      (node (ref "SL1") (pin "6") (pinfunction "6_6") (pintype "passive"))
    )
    (net (code "184") (name "TH4") (class "Default")
      (node (ref "C24") (pin "A") (pinfunction "+_A") (pintype "passive"))
      (node (ref "IC1") (pin "6") (pinfunction "P0[26]/AD0[3]/AOUT/RXD3_6") (pintype "bidirectional"))
      (node (ref "RN1") (pin "5") (pinfunction "2_5") (pintype "passive"))
      (node (ref "SL1") (pin "8") (pinfunction "8_8") (pintype "passive"))
    )
    (net (code "185") (name "TX_0") (class "Default")
      (node (ref "IC1") (pin "98") (pinfunction "P0[2]/TXD0/AD0[7]_98") (pintype "bidirectional"))
      (node (ref "JP5") (pin "5") (pinfunction "5_5") (pintype "passive"))
    )
    (net (code "186") (name "USB_D+") (class "Default")
      (node (ref "C5") (pin "2") (pinfunction "2_2") (pintype "passive"))
      (node (ref "IC1") (pin "29") (pinfunction "P0[29]/USB_D+_29") (pintype "bidirectional"))
      (node (ref "R7") (pin "1") (pinfunction "1_1") (pintype "passive"))
      (node (ref "R8") (pin "2") (pinfunction "2_2") (pintype "passive"))
    )
    (net (code "187") (name "USB_D-") (class "Default")
      (node (ref "C4") (pin "2") (pinfunction "2_2") (pintype "passive"))
      (node (ref "IC1") (pin "30") (pinfunction "P0[30]/USB_D-_30") (pintype "bidirectional"))
      (node (ref "R9") (pin "2") (pinfunction "2_2") (pintype "passive"))
    )
    (net (code "188") (name "VBB") (class "Default")
      (node (ref "C17") (pin "1") (pinfunction "1_1") (pintype "passive"))
      (node (ref "C18") (pin "1") (pinfunction "1_1") (pintype "passive"))
      (node (ref "C26") (pin "+") (pinfunction "+_+") (pintype "passive"))
      (node (ref "C27") (pin "1") (pinfunction "1_1") (pintype "passive"))
      (node (ref "C29") (pin "+") (pinfunction "+_+") (pintype "passive"))
      (node (ref "C30") (pin "1") (pinfunction "1_1") (pintype "passive"))
      (node (ref "C34") (pin "1") (pinfunction "1_1") (pintype "passive"))
      (node (ref "C35") (pin "1") (pinfunction "1_1") (pintype "passive"))
      (node (ref "C39") (pin "+") (pinfunction "+_+") (pintype "passive"))
      (node (ref "C40") (pin "1") (pinfunction "1_1") (pintype "passive"))
      (node (ref "C42") (pin "+") (pinfunction "+_+") (pintype "passive"))
      (node (ref "C43") (pin "1") (pinfunction "1_1") (pintype "passive"))
      (node (ref "C63") (pin "+") (pinfunction "+_+") (pintype "passive"))
      (node (ref "IC2") (pin "P16") (pinfunction "VBB1_P16") (pintype "bidirectional"))
      (node (ref "IC2") (pin "P21") (pinfunction "VBB2_P21") (pintype "bidirectional"))
      (node (ref "IC3") (pin "P16") (pinfunction "VBB1_P16") (pintype "bidirectional"))
      (node (ref "IC3") (pin "P21") (pinfunction "VBB2_P21") (pintype "bidirectional"))
      (node (ref "IC5") (pin "P16") (pinfunction "VBB1_P16") (pintype "bidirectional"))
      (node (ref "IC5") (pin "P21") (pinfunction "VBB2_P21") (pintype "bidirectional"))
      (node (ref "IC6") (pin "P16") (pinfunction "VBB1_P16") (pintype "bidirectional"))
      (node (ref "IC6") (pin "P21") (pinfunction "VBB2_P21") (pintype "bidirectional"))
      (node (ref "JP11") (pin "2") (pinfunction "2_2") (pintype "passive"))
      (node (ref "JP17") (pin "1") (pinfunction "1_1") (pintype "passive"))
      (node (ref "JP27") (pin "2") (pinfunction "2_2") (pintype "passive"))
      (node (ref "JP28") (pin "2") (pinfunction "2_2") (pintype "passive"))
      (node (ref "R78") (pin "2") (pinfunction "2_2") (pintype "passive"))
      (node (ref "U$1") (pin "K") (pinfunction "K_K") (pintype "bidirectional"))
    )
    (net (code "189") (name "VBB_IN") (class "Default")
      (node (ref "J10") (pin "P$4") (pinfunction "GND_P$4") (pintype "bidirectional"))
      (node (ref "POWER") (pin "P$1") (pinfunction "+12V_P$1") (pintype "power_in"))
      (node (ref "U$1") (pin "2") (pinfunction "A_2") (pintype "bidirectional"))
      (node (ref "X11") (pin "1") (pinfunction "1_1") (pintype "passive"))
    )
    (net (code "190") (name "VUSB") (class "Default")
      (node (ref "CN1") (pin "VBUS") (pinfunction "VBUS_VBUS") (pintype "power_in"))
      (node (ref "D1") (pin "A") (pinfunction "A_A") (pintype "passive"))
    )
    (net (code "191") (name "X_MAX") (class "Default")
      (node (ref "IC1") (pin "39") (pinfunction "P1[25]/MC1A/MAT1[1]_39") (pintype "bidirectional"))
      (node (ref "JP14") (pin "3") (pinfunction "3_3") (pintype "passive"))
    )
    (net (code "192") (name "X_MIN") (class "Default")
      (node (ref "IC1") (pin "38") (pinfunction "P1[24]/MCFB2/PWM1[5]/MOSI0_38") (pintype "bidirectional"))
      (node (ref "JP26") (pin "3") (pinfunction "3_3") (pintype "passive"))
    )
    (net (code "193") (name "Y_MAX") (class "Default")
      (node (ref "IC1") (pin "43") (pinfunction "P1[27]/CLKOUT/USB_OVRCR/CAP0[1]_43") (pintype "bidirectional"))
      (node (ref "JP19") (pin "3") (pinfunction "3_3") (pintype "passive"))
    )
    (net (code "194") (name "Y_MIN") (class "Default")
      (node (ref "IC1") (pin "40") (pinfunction "P1[26]/MC1B/PWM1[6]/CAP0[0]_40") (pintype "bidirectional"))
      (node (ref "JP16") (pin "3") (pinfunction "3_3") (pintype "passive"))
    )
    (net (code "195") (name "Z_MAX") (class "Default")
      (node (ref "IC1") (pin "45") (pinfunction "P1[29]/MC2B/PCAP1[1]/MAT0[1]_45") (pintype "bidirectional"))
      (node (ref "JP22") (pin "3") (pinfunction "3_3") (pintype "passive"))
    )
    (net (code "196") (name "Z_MIN") (class "Default")
      (node (ref "IC1") (pin "44") (pinfunction "P1[28]/MC2A/PCAP1[0]/MAT0[0]_44") (pintype "bidirectional"))
      (node (ref "JP21") (pin "3") (pinfunction "3_3") (pintype "passive"))
    )
    (net (code "197") (name "unconnected-(CN1-PadID)") (class "Default")
      (node (ref "CN1") (pin "ID") (pinfunction "ID_ID") (pintype "bidirectional"))
    )
    (net (code "198") (name "unconnected-(IC1-N.C.-Pad13)") (class "Default")
      (node (ref "IC1") (pin "13") (pinfunction "N.C._13") (pintype "bidirectional"))
    )
    (net (code "199") (name "unconnected-(IC1-RTCX1-Pad16)") (class "Default")
      (node (ref "IC1") (pin "16") (pinfunction "RTCX1_16") (pintype "bidirectional"))
    )
    (net (code "200") (name "unconnected-(IC1-RTCX2-Pad18)") (class "Default")
      (node (ref "IC1") (pin "18") (pinfunction "RTCX2_18") (pintype "bidirectional"))
    )
    (net (code "201") (name "unconnected-(IC4-NC-Pad14)") (class "Default")
      (node (ref "IC4") (pin "14") (pinfunction "NC_14") (pintype "bidirectional"))
    )
    (net (code "202") (name "unconnected-(IC7-NC-Pad1)") (class "Default")
      (node (ref "IC7") (pin "1") (pinfunction "NC_1") (pintype "no_connect"))
    )
    (net (code "203") (name "unconnected-(J5-GNDBREAK-PadGND)") (class "Default")
      (node (ref "J5") (pin "GND") (pinfunction "GNDBREAK_GND") (pintype "bidirectional"))
    )
    (net (code "204") (name "unconnected-(J10-GNDBREAK-PadGND)") (class "Default")
      (node (ref "J10") (pin "GND") (pinfunction "GNDBREAK_GND") (pintype "bidirectional"))
    )
    (net (code "205") (name "unconnected-(RJ1-PadNC)") (class "Default")
      (node (ref "RJ1") (pin "NC") (pinfunction "NC_NC") (pintype "bidirectional"))
    )
    (net (code "206") (name "unconnected-(U$1-N{slash}C-Pad1)") (class "Default")
      (node (ref "U$1") (pin "1") (pinfunction "N/C_1") (pintype "bidirectional"))
    )
    (net (code "207") (name "unconnected-(U1-NC-Pad1)") (class "Default")
      (node (ref "U1") (pin "1") (pinfunction "NC_1") (pintype "bidirectional"))
    )
    (net (code "208") (name "unconnected-(U1-RSV-Pad8)") (class "Default")
      (node (ref "U1") (pin "8") (pinfunction "RSV_8") (pintype "bidirectional"))
    )
    (net (code "209") (name "unconnected-(U1-SHIELD-PadCD1)") (class "Default")
      (node (ref "U1") (pin "CD1") (pinfunction "SHIELD_CD1") (pintype "bidirectional"))
    )
    (net (code "210") (name "unconnected-(U1-SHIELD-PadGND3)") (class "Default")
      (node (ref "U1") (pin "GND3") (pinfunction "SHIELD_GND3") (pintype "bidirectional"))
    )
  )
)
